# untitled.net
KiCad netlist of a schematic drawn in EAGLE
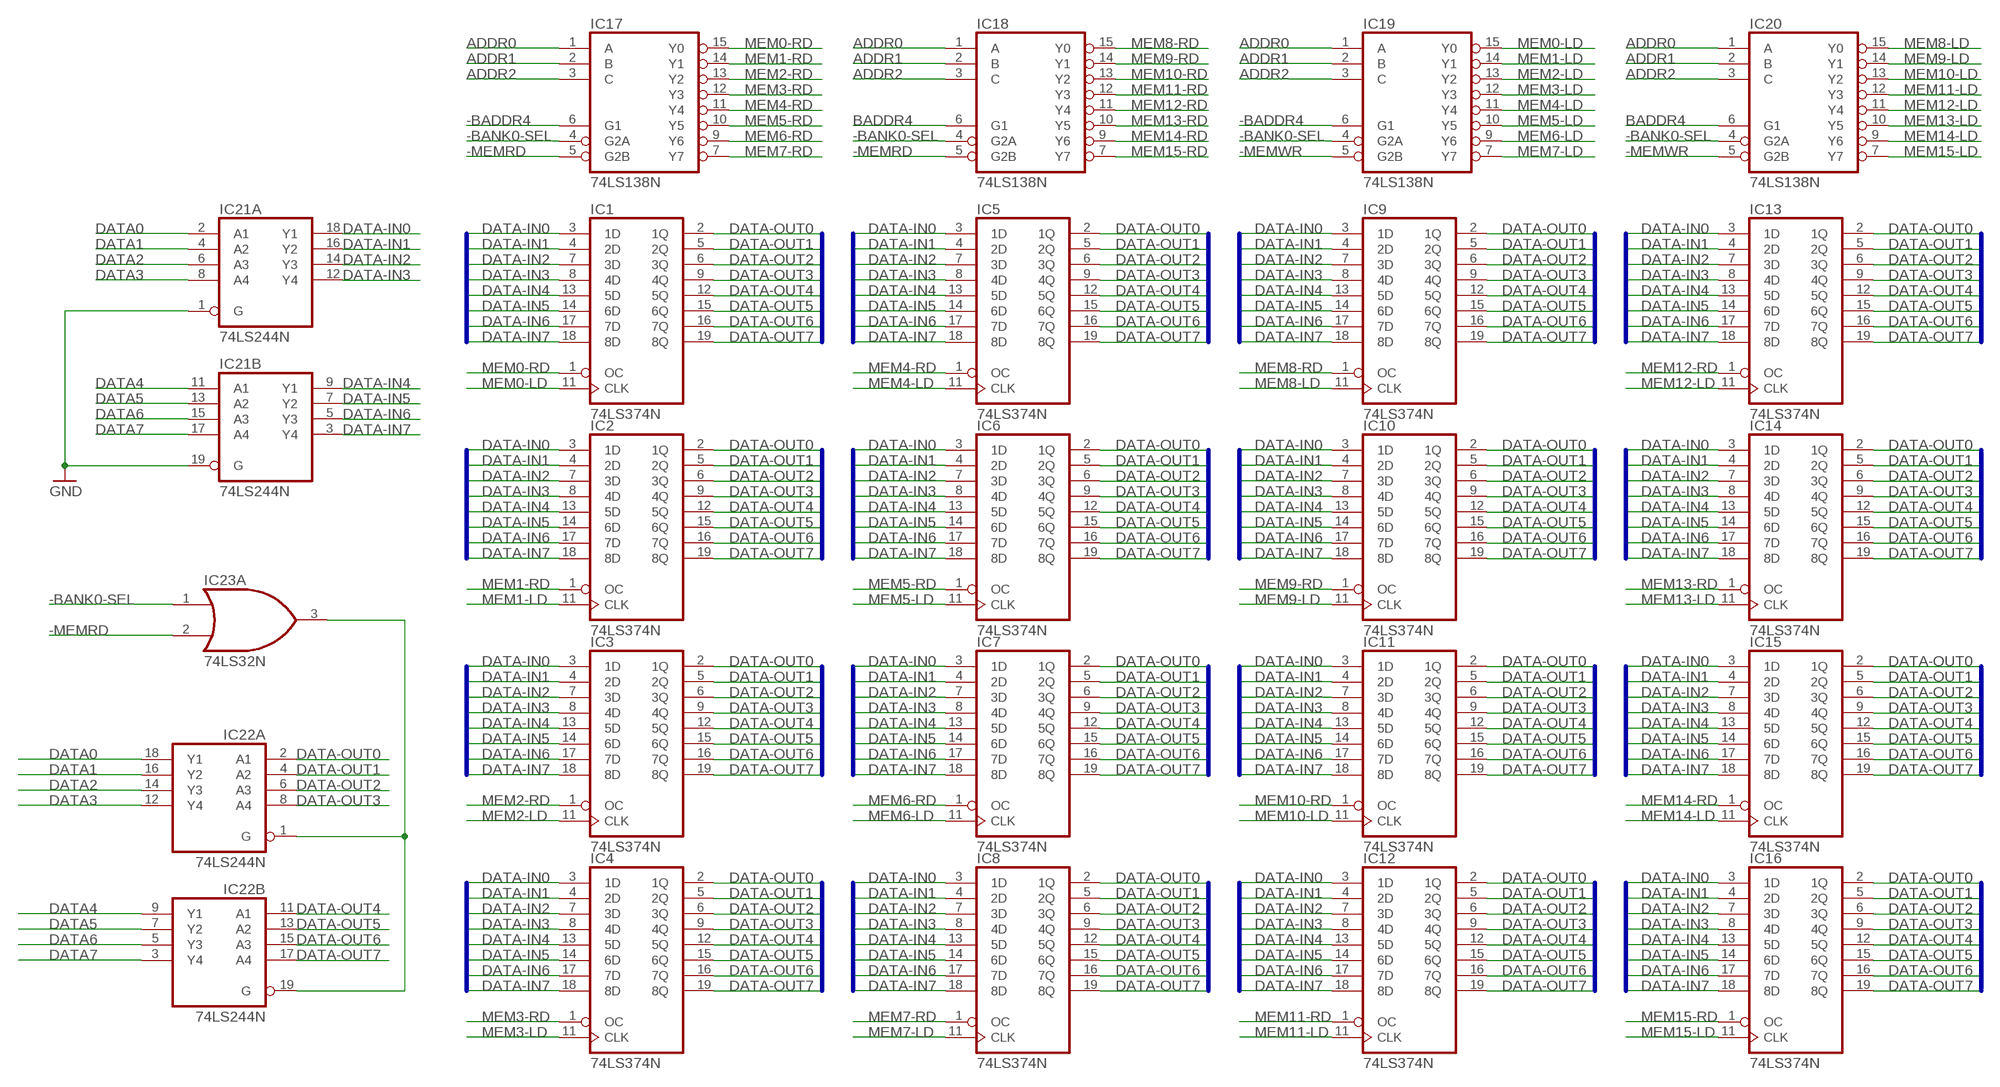
[diagram p0: schematic, sheet 1]
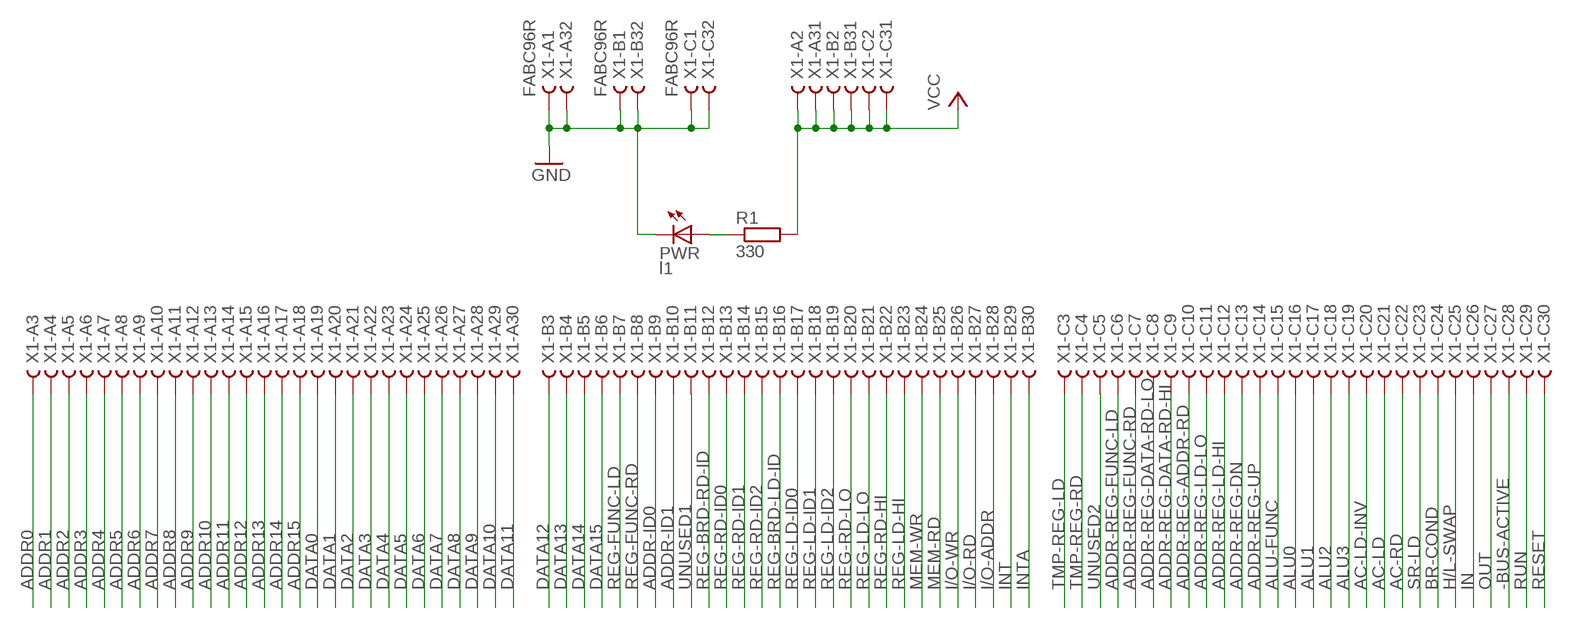
[diagram p1: schematic, sheet 2]
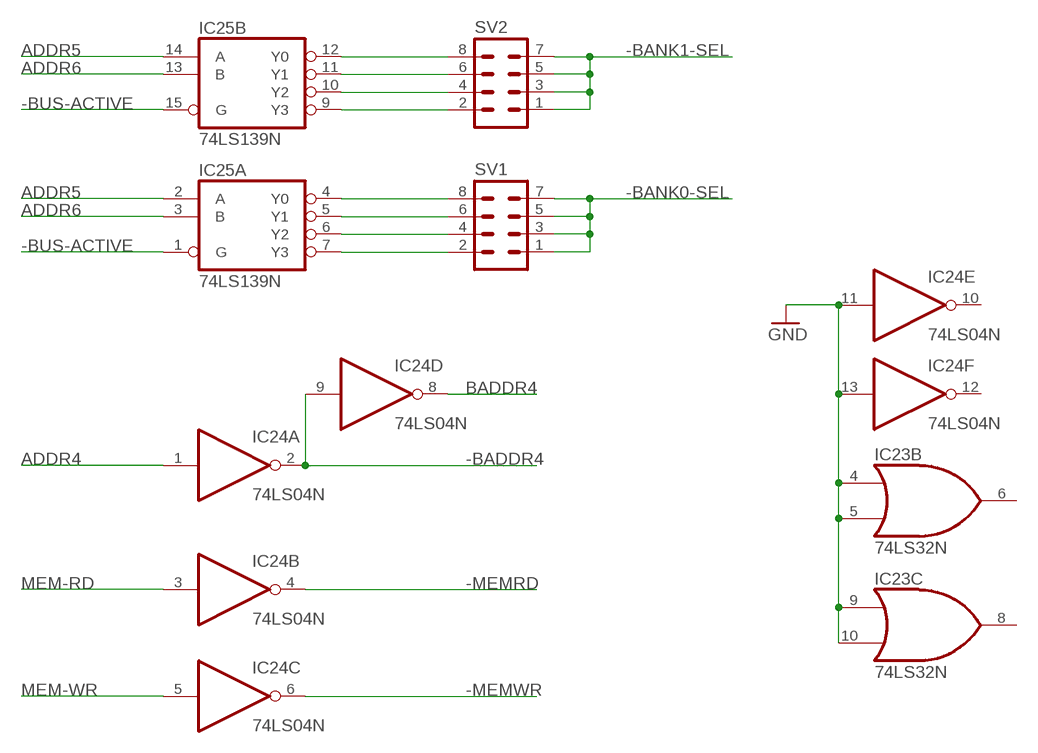
[diagram p2: schematic, sheet 3]
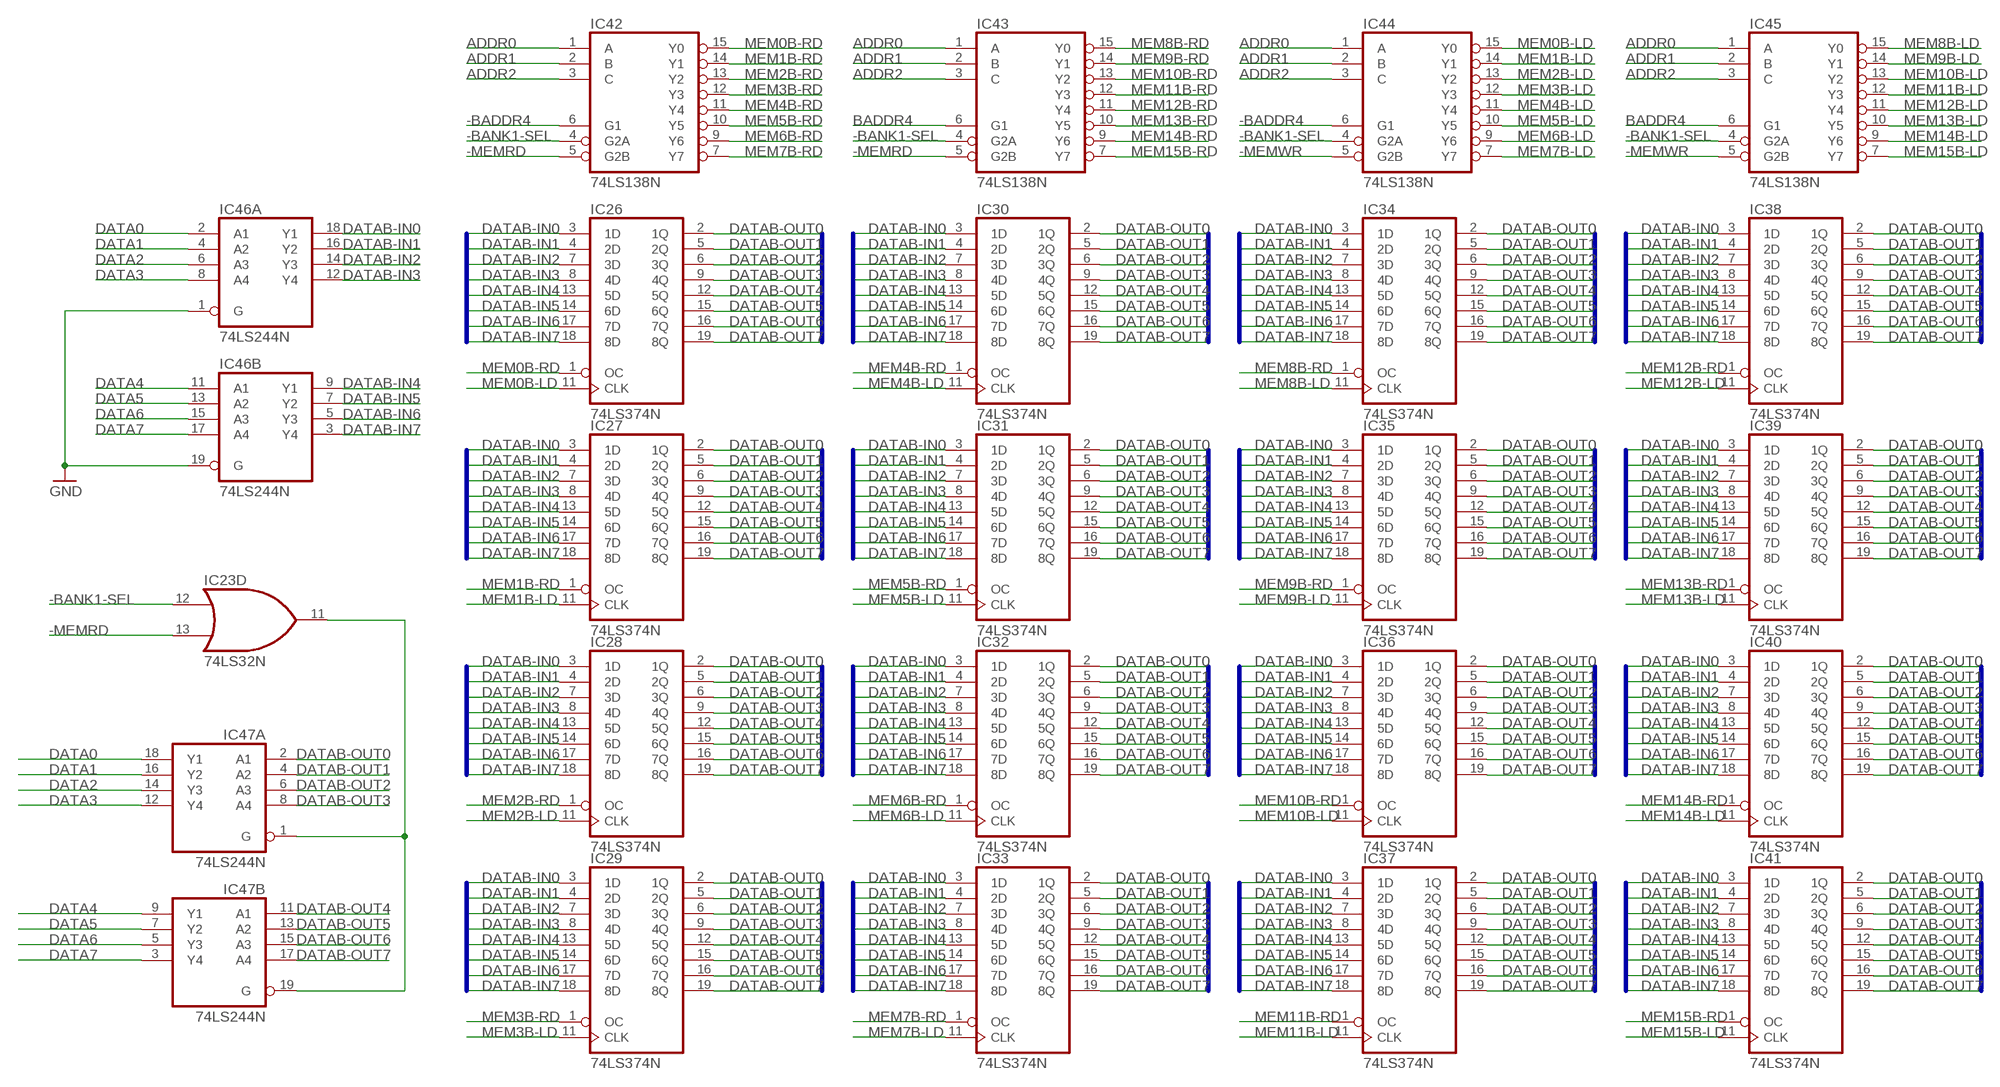
[diagram p3: schematic, sheet 4]

(export (version "E")
  (design (tool "Eeschema 10.0.6"))
  (components
    (comp (ref "PWR")
      (value "l1")
      (footprint "eagle-import:LED5MM")
      (libsource (lib "eagle-import") (part "LED5MM"))
    )
    (comp (ref "R1")
      (value "330")
      (footprint "eagle-import:0207_10")
      (libsource (lib "eagle-import") (part "R0207/10"))
    )
    (comp (ref "X1")
      (value "FABC96R")
      (footprint "eagle-import:FABC96R")
      (libsource (lib "eagle-import") (part "FABC96R"))
    )
    (comp (ref "IC1")
      (value "74LS374N")
      (footprint "eagle-import:DIL20")
      (libsource (lib "eagle-import") (part "74374NLS"))
    )
    (comp (ref "IC2")
      (value "74LS374N")
      (footprint "eagle-import:DIL20")
      (libsource (lib "eagle-import") (part "74374NLS"))
    )
    (comp (ref "IC3")
      (value "74LS374N")
      (footprint "eagle-import:DIL20")
      (libsource (lib "eagle-import") (part "74374NLS"))
    )
    (comp (ref "IC4")
      (value "74LS374N")
      (footprint "eagle-import:DIL20")
      (libsource (lib "eagle-import") (part "74374NLS"))
    )
    (comp (ref "IC5")
      (value "74LS374N")
      (footprint "eagle-import:DIL20")
      (libsource (lib "eagle-import") (part "74374NLS"))
    )
    (comp (ref "IC6")
      (value "74LS374N")
      (footprint "eagle-import:DIL20")
      (libsource (lib "eagle-import") (part "74374NLS"))
    )
    (comp (ref "IC7")
      (value "74LS374N")
      (footprint "eagle-import:DIL20")
      (libsource (lib "eagle-import") (part "74374NLS"))
    )
    (comp (ref "IC8")
      (value "74LS374N")
      (footprint "eagle-import:DIL20")
      (libsource (lib "eagle-import") (part "74374NLS"))
    )
    (comp (ref "IC9")
      (value "74LS374N")
      (footprint "eagle-import:DIL20")
      (libsource (lib "eagle-import") (part "74374NLS"))
    )
    (comp (ref "IC10")
      (value "74LS374N")
      (footprint "eagle-import:DIL20")
      (libsource (lib "eagle-import") (part "74374NLS"))
    )
    (comp (ref "IC11")
      (value "74LS374N")
      (footprint "eagle-import:DIL20")
      (libsource (lib "eagle-import") (part "74374NLS"))
    )
    (comp (ref "IC12")
      (value "74LS374N")
      (footprint "eagle-import:DIL20")
      (libsource (lib "eagle-import") (part "74374NLS"))
    )
    (comp (ref "IC13")
      (value "74LS374N")
      (footprint "eagle-import:DIL20")
      (libsource (lib "eagle-import") (part "74374NLS"))
    )
    (comp (ref "IC14")
      (value "74LS374N")
      (footprint "eagle-import:DIL20")
      (libsource (lib "eagle-import") (part "74374NLS"))
    )
    (comp (ref "IC15")
      (value "74LS374N")
      (footprint "eagle-import:DIL20")
      (libsource (lib "eagle-import") (part "74374NLS"))
    )
    (comp (ref "IC16")
      (value "74LS374N")
      (footprint "eagle-import:DIL20")
      (libsource (lib "eagle-import") (part "74374NLS"))
    )
    (comp (ref "IC17")
      (value "74LS138N")
      (footprint "eagle-import:DIL16")
      (libsource (lib "eagle-import") (part "74138NLS"))
    )
    (comp (ref "IC18")
      (value "74LS138N")
      (footprint "eagle-import:DIL16")
      (libsource (lib "eagle-import") (part "74138NLS"))
    )
    (comp (ref "IC19")
      (value "74LS138N")
      (footprint "eagle-import:DIL16")
      (libsource (lib "eagle-import") (part "74138NLS"))
    )
    (comp (ref "IC20")
      (value "74LS138N")
      (footprint "eagle-import:DIL16")
      (libsource (lib "eagle-import") (part "74138NLS"))
    )
    (comp (ref "IC21")
      (value "74LS244N")
      (footprint "eagle-import:DIL20")
      (libsource (lib "eagle-import") (part "74244NLS"))
    )
    (comp (ref "IC22")
      (value "74LS244N")
      (footprint "eagle-import:DIL20")
      (libsource (lib "eagle-import") (part "74244NLS"))
    )
    (comp (ref "IC23")
      (value "74LS32N")
      (footprint "eagle-import:DIL14")
      (libsource (lib "eagle-import") (part "7432NLS"))
    )
    (comp (ref "IC24")
      (value "74LS04N")
      (footprint "eagle-import:DIL14")
      (libsource (lib "eagle-import") (part "7404NLS"))
    )
    (comp (ref "IC25")
      (value "74LS139N")
      (footprint "eagle-import:DIL16")
      (libsource (lib "eagle-import") (part "74139NLS"))
    )
    (comp (ref "SV1")
      (value "MA04-2")
      (footprint "eagle-import:MA04-2")
      (libsource (lib "eagle-import") (part "MA04-2"))
    )
    (comp (ref "SV2")
      (value "MA04-2")
      (footprint "eagle-import:MA04-2")
      (libsource (lib "eagle-import") (part "MA04-2"))
    )
    (comp (ref "IC26")
      (value "74LS374N")
      (footprint "eagle-import:DIL20")
      (libsource (lib "eagle-import") (part "74374NLS"))
    )
    (comp (ref "IC27")
      (value "74LS374N")
      (footprint "eagle-import:DIL20")
      (libsource (lib "eagle-import") (part "74374NLS"))
    )
    (comp (ref "IC28")
      (value "74LS374N")
      (footprint "eagle-import:DIL20")
      (libsource (lib "eagle-import") (part "74374NLS"))
    )
    (comp (ref "IC29")
      (value "74LS374N")
      (footprint "eagle-import:DIL20")
      (libsource (lib "eagle-import") (part "74374NLS"))
    )
    (comp (ref "IC30")
      (value "74LS374N")
      (footprint "eagle-import:DIL20")
      (libsource (lib "eagle-import") (part "74374NLS"))
    )
    (comp (ref "IC31")
      (value "74LS374N")
      (footprint "eagle-import:DIL20")
      (libsource (lib "eagle-import") (part "74374NLS"))
    )
    (comp (ref "IC32")
      (value "74LS374N")
      (footprint "eagle-import:DIL20")
      (libsource (lib "eagle-import") (part "74374NLS"))
    )
    (comp (ref "IC33")
      (value "74LS374N")
      (footprint "eagle-import:DIL20")
      (libsource (lib "eagle-import") (part "74374NLS"))
    )
    (comp (ref "IC34")
      (value "74LS374N")
      (footprint "eagle-import:DIL20")
      (libsource (lib "eagle-import") (part "74374NLS"))
    )
    (comp (ref "IC35")
      (value "74LS374N")
      (footprint "eagle-import:DIL20")
      (libsource (lib "eagle-import") (part "74374NLS"))
    )
    (comp (ref "IC36")
      (value "74LS374N")
      (footprint "eagle-import:DIL20")
      (libsource (lib "eagle-import") (part "74374NLS"))
    )
    (comp (ref "IC37")
      (value "74LS374N")
      (footprint "eagle-import:DIL20")
      (libsource (lib "eagle-import") (part "74374NLS"))
    )
    (comp (ref "IC38")
      (value "74LS374N")
      (footprint "eagle-import:DIL20")
      (libsource (lib "eagle-import") (part "74374NLS"))
    )
    (comp (ref "IC39")
      (value "74LS374N")
      (footprint "eagle-import:DIL20")
      (libsource (lib "eagle-import") (part "74374NLS"))
    )
    (comp (ref "IC40")
      (value "74LS374N")
      (footprint "eagle-import:DIL20")
      (libsource (lib "eagle-import") (part "74374NLS"))
    )
    (comp (ref "IC41")
      (value "74LS374N")
      (footprint "eagle-import:DIL20")
      (libsource (lib "eagle-import") (part "74374NLS"))
    )
    (comp (ref "IC42")
      (value "74LS138N")
      (footprint "eagle-import:DIL16")
      (libsource (lib "eagle-import") (part "74138NLS"))
    )
    (comp (ref "IC43")
      (value "74LS138N")
      (footprint "eagle-import:DIL16")
      (libsource (lib "eagle-import") (part "74138NLS"))
    )
    (comp (ref "IC44")
      (value "74LS138N")
      (footprint "eagle-import:DIL16")
      (libsource (lib "eagle-import") (part "74138NLS"))
    )
    (comp (ref "IC45")
      (value "74LS138N")
      (footprint "eagle-import:DIL16")
      (libsource (lib "eagle-import") (part "74138NLS"))
    )
    (comp (ref "IC46")
      (value "74LS244N")
      (footprint "eagle-import:DIL20")
      (libsource (lib "eagle-import") (part "74244NLS"))
    )
    (comp (ref "IC47")
      (value "74LS244N")
      (footprint "eagle-import:DIL20")
      (libsource (lib "eagle-import") (part "74244NLS"))
    )
  )
  (nets
    (net (code "1") (name "-BADDR4") (class "Default")
      (node (ref "IC17") (pin "6") (pinfunction "G1_6") (pintype "input"))
      (node (ref "IC19") (pin "6") (pinfunction "G1_6") (pintype "input"))
      (node (ref "IC24") (pin "2") (pinfunction "O_2") (pintype "output"))
      (node (ref "IC24") (pin "9") (pinfunction "I_9") (pintype "input"))
      (node (ref "IC42") (pin "6") (pinfunction "G1_6") (pintype "input"))
      (node (ref "IC44") (pin "6") (pinfunction "G1_6") (pintype "input"))
    )
    (net (code "2") (name "-BANK0-SEL") (class "Default")
      (node (ref "IC17") (pin "4") (pinfunction "G2A_4") (pintype "input"))
      (node (ref "IC18") (pin "4") (pinfunction "G2A_4") (pintype "input"))
      (node (ref "IC19") (pin "4") (pinfunction "G2A_4") (pintype "input"))
      (node (ref "IC20") (pin "4") (pinfunction "G2A_4") (pintype "input"))
      (node (ref "IC23") (pin "1") (pinfunction "I0_1") (pintype "input"))
      (node (ref "SV1") (pin "1") (pinfunction "1_1") (pintype "passive"))
      (node (ref "SV1") (pin "3") (pinfunction "3_3") (pintype "passive"))
      (node (ref "SV1") (pin "5") (pinfunction "5_5") (pintype "passive"))
      (node (ref "SV1") (pin "7") (pinfunction "7_7") (pintype "passive"))
    )
    (net (code "3") (name "-BANK1-SEL") (class "Default")
      (node (ref "IC23") (pin "12") (pinfunction "I0_12") (pintype "input"))
      (node (ref "IC42") (pin "4") (pinfunction "G2A_4") (pintype "input"))
      (node (ref "IC43") (pin "4") (pinfunction "G2A_4") (pintype "input"))
      (node (ref "IC44") (pin "4") (pinfunction "G2A_4") (pintype "input"))
      (node (ref "IC45") (pin "4") (pinfunction "G2A_4") (pintype "input"))
      (node (ref "SV2") (pin "1") (pinfunction "1_1") (pintype "passive"))
      (node (ref "SV2") (pin "3") (pinfunction "3_3") (pintype "passive"))
      (node (ref "SV2") (pin "5") (pinfunction "5_5") (pintype "passive"))
      (node (ref "SV2") (pin "7") (pinfunction "7_7") (pintype "passive"))
    )
    (net (code "4") (name "-BUS-ACTIVE") (class "Default")
      (node (ref "IC25") (pin "1") (pinfunction "G_1") (pintype "input"))
      (node (ref "IC25") (pin "15") (pinfunction "G_15") (pintype "input"))
      (node (ref "X1") (pin "C28") (pinfunction "B_C28") (pintype "passive"))
    )
    (net (code "5") (name "-MEMRD") (class "Default")
      (node (ref "IC17") (pin "5") (pinfunction "G2B_5") (pintype "input"))
      (node (ref "IC18") (pin "5") (pinfunction "G2B_5") (pintype "input"))
      (node (ref "IC23") (pin "13") (pinfunction "I1_13") (pintype "input"))
      (node (ref "IC23") (pin "2") (pinfunction "I1_2") (pintype "input"))
      (node (ref "IC24") (pin "4") (pinfunction "O_4") (pintype "output"))
      (node (ref "IC42") (pin "5") (pinfunction "G2B_5") (pintype "input"))
      (node (ref "IC43") (pin "5") (pinfunction "G2B_5") (pintype "input"))
    )
    (net (code "6") (name "-MEMWR") (class "Default")
      (node (ref "IC19") (pin "5") (pinfunction "G2B_5") (pintype "input"))
      (node (ref "IC20") (pin "5") (pinfunction "G2B_5") (pintype "input"))
      (node (ref "IC24") (pin "6") (pinfunction "O_6") (pintype "output"))
      (node (ref "IC44") (pin "5") (pinfunction "G2B_5") (pintype "input"))
      (node (ref "IC45") (pin "5") (pinfunction "G2B_5") (pintype "input"))
    )
    (net (code "7") (name "AC-LD") (class "Default")
      (node (ref "X1") (pin "C21") (pinfunction "B_C21") (pintype "passive"))
    )
    (net (code "8") (name "AC-LD-INV") (class "Default")
      (node (ref "X1") (pin "C20") (pinfunction "B_C20") (pintype "passive"))
    )
    (net (code "9") (name "AC-RD") (class "Default")
      (node (ref "X1") (pin "C22") (pinfunction "B_C22") (pintype "passive"))
    )
    (net (code "10") (name "ADDR-ID0") (class "Default")
      (node (ref "X1") (pin "B9") (pinfunction "B_B9") (pintype "passive"))
    )
    (net (code "11") (name "ADDR-ID1") (class "Default")
      (node (ref "X1") (pin "B10") (pinfunction "B_B10") (pintype "passive"))
    )
    (net (code "12") (name "ADDR-REG-ADDR-RD") (class "Default")
      (node (ref "X1") (pin "C10") (pinfunction "B_C10") (pintype "passive"))
    )
    (net (code "13") (name "ADDR-REG-DATA-RD-HI") (class "Default")
      (node (ref "X1") (pin "C9") (pinfunction "B_C9") (pintype "passive"))
    )
    (net (code "14") (name "ADDR-REG-DATA-RD-LO") (class "Default")
      (node (ref "X1") (pin "C8") (pinfunction "B_C8") (pintype "passive"))
    )
    (net (code "15") (name "ADDR-REG-DN") (class "Default")
      (node (ref "X1") (pin "C13") (pinfunction "B_C13") (pintype "passive"))
    )
    (net (code "16") (name "ADDR-REG-FUNC-LD") (class "Default")
      (node (ref "X1") (pin "C6") (pinfunction "B_C6") (pintype "passive"))
    )
    (net (code "17") (name "ADDR-REG-FUNC-RD") (class "Default")
      (node (ref "X1") (pin "C7") (pinfunction "B_C7") (pintype "passive"))
    )
    (net (code "18") (name "ADDR-REG-LD-HI") (class "Default")
      (node (ref "X1") (pin "C12") (pinfunction "B_C12") (pintype "passive"))
    )
    (net (code "19") (name "ADDR-REG-LD-LO") (class "Default")
      (node (ref "X1") (pin "C11") (pinfunction "B_C11") (pintype "passive"))
    )
    (net (code "20") (name "ADDR-REG-UP") (class "Default")
      (node (ref "X1") (pin "C14") (pinfunction "B_C14") (pintype "passive"))
    )
    (net (code "21") (name "ADDR0") (class "Default")
      (node (ref "IC17") (pin "1") (pinfunction "A_1") (pintype "input"))
      (node (ref "IC18") (pin "1") (pinfunction "A_1") (pintype "input"))
      (node (ref "IC19") (pin "1") (pinfunction "A_1") (pintype "input"))
      (node (ref "IC20") (pin "1") (pinfunction "A_1") (pintype "input"))
      (node (ref "IC42") (pin "1") (pinfunction "A_1") (pintype "input"))
      (node (ref "IC43") (pin "1") (pinfunction "A_1") (pintype "input"))
      (node (ref "IC44") (pin "1") (pinfunction "A_1") (pintype "input"))
      (node (ref "IC45") (pin "1") (pinfunction "A_1") (pintype "input"))
      (node (ref "X1") (pin "A3") (pinfunction "B_A3") (pintype "passive"))
    )
    (net (code "22") (name "ADDR1") (class "Default")
      (node (ref "IC17") (pin "2") (pinfunction "B_2") (pintype "input"))
      (node (ref "IC18") (pin "2") (pinfunction "B_2") (pintype "input"))
      (node (ref "IC19") (pin "2") (pinfunction "B_2") (pintype "input"))
      (node (ref "IC20") (pin "2") (pinfunction "B_2") (pintype "input"))
      (node (ref "IC42") (pin "2") (pinfunction "B_2") (pintype "input"))
      (node (ref "IC43") (pin "2") (pinfunction "B_2") (pintype "input"))
      (node (ref "IC44") (pin "2") (pinfunction "B_2") (pintype "input"))
      (node (ref "IC45") (pin "2") (pinfunction "B_2") (pintype "input"))
      (node (ref "X1") (pin "A4") (pinfunction "B_A4") (pintype "passive"))
    )
    (net (code "23") (name "ADDR2") (class "Default")
      (node (ref "IC17") (pin "3") (pinfunction "C_3") (pintype "input"))
      (node (ref "IC18") (pin "3") (pinfunction "C_3") (pintype "input"))
      (node (ref "IC19") (pin "3") (pinfunction "C_3") (pintype "input"))
      (node (ref "IC20") (pin "3") (pinfunction "C_3") (pintype "input"))
      (node (ref "IC42") (pin "3") (pinfunction "C_3") (pintype "input"))
      (node (ref "IC43") (pin "3") (pinfunction "C_3") (pintype "input"))
      (node (ref "IC44") (pin "3") (pinfunction "C_3") (pintype "input"))
      (node (ref "IC45") (pin "3") (pinfunction "C_3") (pintype "input"))
      (node (ref "X1") (pin "A5") (pinfunction "B_A5") (pintype "passive"))
    )
    (net (code "24") (name "ADDR3") (class "Default")
      (node (ref "X1") (pin "A6") (pinfunction "B_A6") (pintype "passive"))
    )
    (net (code "25") (name "ADDR4") (class "Default")
      (node (ref "IC24") (pin "1") (pinfunction "I_1") (pintype "input"))
      (node (ref "X1") (pin "A7") (pinfunction "B_A7") (pintype "passive"))
    )
    (net (code "26") (name "ADDR5") (class "Default")
      (node (ref "IC25") (pin "14") (pinfunction "A_14") (pintype "input"))
      (node (ref "IC25") (pin "2") (pinfunction "A_2") (pintype "input"))
      (node (ref "X1") (pin "A8") (pinfunction "B_A8") (pintype "passive"))
    )
    (net (code "27") (name "ADDR6") (class "Default")
      (node (ref "IC25") (pin "13") (pinfunction "B_13") (pintype "input"))
      (node (ref "IC25") (pin "3") (pinfunction "B_3") (pintype "input"))
      (node (ref "X1") (pin "A9") (pinfunction "B_A9") (pintype "passive"))
    )
    (net (code "28") (name "ADDR7") (class "Default")
      (node (ref "X1") (pin "A10") (pinfunction "B_A10") (pintype "passive"))
    )
    (net (code "29") (name "ADDR8") (class "Default")
      (node (ref "X1") (pin "A11") (pinfunction "B_A11") (pintype "passive"))
    )
    (net (code "30") (name "ADDR9") (class "Default")
      (node (ref "X1") (pin "A12") (pinfunction "B_A12") (pintype "passive"))
    )
    (net (code "31") (name "ADDR10") (class "Default")
      (node (ref "X1") (pin "A13") (pinfunction "B_A13") (pintype "passive"))
    )
    (net (code "32") (name "ADDR11") (class "Default")
      (node (ref "X1") (pin "A14") (pinfunction "B_A14") (pintype "passive"))
    )
    (net (code "33") (name "ADDR12") (class "Default")
      (node (ref "X1") (pin "A15") (pinfunction "B_A15") (pintype "passive"))
    )
    (net (code "34") (name "ADDR13") (class "Default")
      (node (ref "X1") (pin "A16") (pinfunction "B_A16") (pintype "passive"))
    )
    (net (code "35") (name "ADDR14") (class "Default")
      (node (ref "X1") (pin "A17") (pinfunction "B_A17") (pintype "passive"))
    )
    (net (code "36") (name "ADDR15") (class "Default")
      (node (ref "X1") (pin "A18") (pinfunction "B_A18") (pintype "passive"))
    )
    (net (code "37") (name "ALU-FUNC") (class "Default")
      (node (ref "X1") (pin "C15") (pinfunction "B_C15") (pintype "passive"))
    )
    (net (code "38") (name "ALU0") (class "Default")
      (node (ref "X1") (pin "C16") (pinfunction "B_C16") (pintype "passive"))
    )
    (net (code "39") (name "ALU1") (class "Default")
      (node (ref "X1") (pin "C17") (pinfunction "B_C17") (pintype "passive"))
    )
    (net (code "40") (name "ALU2") (class "Default")
      (node (ref "X1") (pin "C18") (pinfunction "B_C18") (pintype "passive"))
    )
    (net (code "41") (name "ALU3") (class "Default")
      (node (ref "X1") (pin "C19") (pinfunction "B_C19") (pintype "passive"))
    )
    (net (code "42") (name "BADDR4") (class "Default")
      (node (ref "IC18") (pin "6") (pinfunction "G1_6") (pintype "input"))
      (node (ref "IC20") (pin "6") (pinfunction "G1_6") (pintype "input"))
      (node (ref "IC24") (pin "8") (pinfunction "O_8") (pintype "output"))
      (node (ref "IC43") (pin "6") (pinfunction "G1_6") (pintype "input"))
      (node (ref "IC45") (pin "6") (pinfunction "G1_6") (pintype "input"))
    )
    (net (code "43") (name "BR-COND") (class "Default")
      (node (ref "X1") (pin "C24") (pinfunction "B_C24") (pintype "passive"))
    )
    (net (code "44") (name "DATA-IN0") (class "Default")
      (node (ref "IC1") (pin "3") (pinfunction "1D_3") (pintype "input"))
      (node (ref "IC10") (pin "3") (pinfunction "1D_3") (pintype "input"))
      (node (ref "IC11") (pin "3") (pinfunction "1D_3") (pintype "input"))
      (node (ref "IC12") (pin "3") (pinfunction "1D_3") (pintype "input"))
      (node (ref "IC13") (pin "3") (pinfunction "1D_3") (pintype "input"))
      (node (ref "IC14") (pin "3") (pinfunction "1D_3") (pintype "input"))
      (node (ref "IC15") (pin "3") (pinfunction "1D_3") (pintype "input"))
      (node (ref "IC16") (pin "3") (pinfunction "1D_3") (pintype "input"))
      (node (ref "IC2") (pin "3") (pinfunction "1D_3") (pintype "input"))
      (node (ref "IC21") (pin "18") (pinfunction "Y1_18") (pintype "tri_state"))
      (node (ref "IC3") (pin "3") (pinfunction "1D_3") (pintype "input"))
      (node (ref "IC4") (pin "3") (pinfunction "1D_3") (pintype "input"))
      (node (ref "IC5") (pin "3") (pinfunction "1D_3") (pintype "input"))
      (node (ref "IC6") (pin "3") (pinfunction "1D_3") (pintype "input"))
      (node (ref "IC7") (pin "3") (pinfunction "1D_3") (pintype "input"))
      (node (ref "IC8") (pin "3") (pinfunction "1D_3") (pintype "input"))
      (node (ref "IC9") (pin "3") (pinfunction "1D_3") (pintype "input"))
    )
    (net (code "45") (name "DATA-IN1") (class "Default")
      (node (ref "IC1") (pin "4") (pinfunction "2D_4") (pintype "input"))
      (node (ref "IC10") (pin "4") (pinfunction "2D_4") (pintype "input"))
      (node (ref "IC11") (pin "4") (pinfunction "2D_4") (pintype "input"))
      (node (ref "IC12") (pin "4") (pinfunction "2D_4") (pintype "input"))
      (node (ref "IC13") (pin "4") (pinfunction "2D_4") (pintype "input"))
      (node (ref "IC14") (pin "4") (pinfunction "2D_4") (pintype "input"))
      (node (ref "IC15") (pin "4") (pinfunction "2D_4") (pintype "input"))
      (node (ref "IC16") (pin "4") (pinfunction "2D_4") (pintype "input"))
      (node (ref "IC2") (pin "4") (pinfunction "2D_4") (pintype "input"))
      (node (ref "IC21") (pin "16") (pinfunction "Y2_16") (pintype "tri_state"))
      (node (ref "IC3") (pin "4") (pinfunction "2D_4") (pintype "input"))
      (node (ref "IC4") (pin "4") (pinfunction "2D_4") (pintype "input"))
      (node (ref "IC5") (pin "4") (pinfunction "2D_4") (pintype "input"))
      (node (ref "IC6") (pin "4") (pinfunction "2D_4") (pintype "input"))
      (node (ref "IC7") (pin "4") (pinfunction "2D_4") (pintype "input"))
      (node (ref "IC8") (pin "4") (pinfunction "2D_4") (pintype "input"))
      (node (ref "IC9") (pin "4") (pinfunction "2D_4") (pintype "input"))
    )
    (net (code "46") (name "DATA-IN2") (class "Default")
      (node (ref "IC1") (pin "7") (pinfunction "3D_7") (pintype "input"))
      (node (ref "IC10") (pin "7") (pinfunction "3D_7") (pintype "input"))
      (node (ref "IC11") (pin "7") (pinfunction "3D_7") (pintype "input"))
      (node (ref "IC12") (pin "7") (pinfunction "3D_7") (pintype "input"))
      (node (ref "IC13") (pin "7") (pinfunction "3D_7") (pintype "input"))
      (node (ref "IC14") (pin "7") (pinfunction "3D_7") (pintype "input"))
      (node (ref "IC15") (pin "7") (pinfunction "3D_7") (pintype "input"))
      (node (ref "IC16") (pin "7") (pinfunction "3D_7") (pintype "input"))
      (node (ref "IC2") (pin "7") (pinfunction "3D_7") (pintype "input"))
      (node (ref "IC21") (pin "14") (pinfunction "Y3_14") (pintype "tri_state"))
      (node (ref "IC3") (pin "7") (pinfunction "3D_7") (pintype "input"))
      (node (ref "IC4") (pin "7") (pinfunction "3D_7") (pintype "input"))
      (node (ref "IC5") (pin "7") (pinfunction "3D_7") (pintype "input"))
      (node (ref "IC6") (pin "7") (pinfunction "3D_7") (pintype "input"))
      (node (ref "IC7") (pin "7") (pinfunction "3D_7") (pintype "input"))
      (node (ref "IC8") (pin "7") (pinfunction "3D_7") (pintype "input"))
      (node (ref "IC9") (pin "7") (pinfunction "3D_7") (pintype "input"))
    )
    (net (code "47") (name "DATA-IN3") (class "Default")
      (node (ref "IC1") (pin "8") (pinfunction "4D_8") (pintype "input"))
      (node (ref "IC10") (pin "8") (pinfunction "4D_8") (pintype "input"))
      (node (ref "IC11") (pin "8") (pinfunction "4D_8") (pintype "input"))
      (node (ref "IC12") (pin "8") (pinfunction "4D_8") (pintype "input"))
      (node (ref "IC13") (pin "8") (pinfunction "4D_8") (pintype "input"))
      (node (ref "IC14") (pin "8") (pinfunction "4D_8") (pintype "input"))
      (node (ref "IC15") (pin "8") (pinfunction "4D_8") (pintype "input"))
      (node (ref "IC16") (pin "8") (pinfunction "4D_8") (pintype "input"))
      (node (ref "IC2") (pin "8") (pinfunction "4D_8") (pintype "input"))
      (node (ref "IC21") (pin "12") (pinfunction "Y4_12") (pintype "tri_state"))
      (node (ref "IC3") (pin "8") (pinfunction "4D_8") (pintype "input"))
      (node (ref "IC4") (pin "8") (pinfunction "4D_8") (pintype "input"))
      (node (ref "IC5") (pin "8") (pinfunction "4D_8") (pintype "input"))
      (node (ref "IC6") (pin "8") (pinfunction "4D_8") (pintype "input"))
      (node (ref "IC7") (pin "8") (pinfunction "4D_8") (pintype "input"))
      (node (ref "IC8") (pin "8") (pinfunction "4D_8") (pintype "input"))
      (node (ref "IC9") (pin "8") (pinfunction "4D_8") (pintype "input"))
    )
    (net (code "48") (name "DATA-IN4") (class "Default")
      (node (ref "IC1") (pin "13") (pinfunction "5D_13") (pintype "input"))
      (node (ref "IC10") (pin "13") (pinfunction "5D_13") (pintype "input"))
      (node (ref "IC11") (pin "13") (pinfunction "5D_13") (pintype "input"))
      (node (ref "IC12") (pin "13") (pinfunction "5D_13") (pintype "input"))
      (node (ref "IC13") (pin "13") (pinfunction "5D_13") (pintype "input"))
      (node (ref "IC14") (pin "13") (pinfunction "5D_13") (pintype "input"))
      (node (ref "IC15") (pin "13") (pinfunction "5D_13") (pintype "input"))
      (node (ref "IC16") (pin "13") (pinfunction "5D_13") (pintype "input"))
      (node (ref "IC2") (pin "13") (pinfunction "5D_13") (pintype "input"))
      (node (ref "IC21") (pin "9") (pinfunction "Y1_9") (pintype "tri_state"))
      (node (ref "IC3") (pin "13") (pinfunction "5D_13") (pintype "input"))
      (node (ref "IC4") (pin "13") (pinfunction "5D_13") (pintype "input"))
      (node (ref "IC5") (pin "13") (pinfunction "5D_13") (pintype "input"))
      (node (ref "IC6") (pin "13") (pinfunction "5D_13") (pintype "input"))
      (node (ref "IC7") (pin "13") (pinfunction "5D_13") (pintype "input"))
      (node (ref "IC8") (pin "13") (pinfunction "5D_13") (pintype "input"))
      (node (ref "IC9") (pin "13") (pinfunction "5D_13") (pintype "input"))
    )
    (net (code "49") (name "DATA-IN5") (class "Default")
      (node (ref "IC1") (pin "14") (pinfunction "6D_14") (pintype "input"))
      (node (ref "IC10") (pin "14") (pinfunction "6D_14") (pintype "input"))
      (node (ref "IC11") (pin "14") (pinfunction "6D_14") (pintype "input"))
      (node (ref "IC12") (pin "14") (pinfunction "6D_14") (pintype "input"))
      (node (ref "IC13") (pin "14") (pinfunction "6D_14") (pintype "input"))
      (node (ref "IC14") (pin "14") (pinfunction "6D_14") (pintype "input"))
      (node (ref "IC15") (pin "14") (pinfunction "6D_14") (pintype "input"))
      (node (ref "IC16") (pin "14") (pinfunction "6D_14") (pintype "input"))
      (node (ref "IC2") (pin "14") (pinfunction "6D_14") (pintype "input"))
      (node (ref "IC21") (pin "7") (pinfunction "Y2_7") (pintype "tri_state"))
      (node (ref "IC3") (pin "14") (pinfunction "6D_14") (pintype "input"))
      (node (ref "IC4") (pin "14") (pinfunction "6D_14") (pintype "input"))
      (node (ref "IC5") (pin "14") (pinfunction "6D_14") (pintype "input"))
      (node (ref "IC6") (pin "14") (pinfunction "6D_14") (pintype "input"))
      (node (ref "IC7") (pin "14") (pinfunction "6D_14") (pintype "input"))
      (node (ref "IC8") (pin "14") (pinfunction "6D_14") (pintype "input"))
      (node (ref "IC9") (pin "14") (pinfunction "6D_14") (pintype "input"))
    )
    (net (code "50") (name "DATA-IN6") (class "Default")
      (node (ref "IC1") (pin "17") (pinfunction "7D_17") (pintype "input"))
      (node (ref "IC10") (pin "17") (pinfunction "7D_17") (pintype "input"))
      (node (ref "IC11") (pin "17") (pinfunction "7D_17") (pintype "input"))
      (node (ref "IC12") (pin "17") (pinfunction "7D_17") (pintype "input"))
      (node (ref "IC13") (pin "17") (pinfunction "7D_17") (pintype "input"))
      (node (ref "IC14") (pin "17") (pinfunction "7D_17") (pintype "input"))
      (node (ref "IC15") (pin "17") (pinfunction "7D_17") (pintype "input"))
      (node (ref "IC16") (pin "17") (pinfunction "7D_17") (pintype "input"))
      (node (ref "IC2") (pin "17") (pinfunction "7D_17") (pintype "input"))
      (node (ref "IC21") (pin "5") (pinfunction "Y3_5") (pintype "tri_state"))
      (node (ref "IC3") (pin "17") (pinfunction "7D_17") (pintype "input"))
      (node (ref "IC4") (pin "17") (pinfunction "7D_17") (pintype "input"))
      (node (ref "IC5") (pin "17") (pinfunction "7D_17") (pintype "input"))
      (node (ref "IC6") (pin "17") (pinfunction "7D_17") (pintype "input"))
      (node (ref "IC7") (pin "17") (pinfunction "7D_17") (pintype "input"))
      (node (ref "IC8") (pin "17") (pinfunction "7D_17") (pintype "input"))
      (node (ref "IC9") (pin "17") (pinfunction "7D_17") (pintype "input"))
    )
    (net (code "51") (name "DATA-IN7") (class "Default")
      (node (ref "IC1") (pin "18") (pinfunction "8D_18") (pintype "input"))
      (node (ref "IC10") (pin "18") (pinfunction "8D_18") (pintype "input"))
      (node (ref "IC11") (pin "18") (pinfunction "8D_18") (pintype "input"))
      (node (ref "IC12") (pin "18") (pinfunction "8D_18") (pintype "input"))
      (node (ref "IC13") (pin "18") (pinfunction "8D_18") (pintype "input"))
      (node (ref "IC14") (pin "18") (pinfunction "8D_18") (pintype "input"))
      (node (ref "IC15") (pin "18") (pinfunction "8D_18") (pintype "input"))
      (node (ref "IC16") (pin "18") (pinfunction "8D_18") (pintype "input"))
      (node (ref "IC2") (pin "18") (pinfunction "8D_18") (pintype "input"))
      (node (ref "IC21") (pin "3") (pinfunction "Y4_3") (pintype "tri_state"))
      (node (ref "IC3") (pin "18") (pinfunction "8D_18") (pintype "input"))
      (node (ref "IC4") (pin "18") (pinfunction "8D_18") (pintype "input"))
      (node (ref "IC5") (pin "18") (pinfunction "8D_18") (pintype "input"))
      (node (ref "IC6") (pin "18") (pinfunction "8D_18") (pintype "input"))
      (node (ref "IC7") (pin "18") (pinfunction "8D_18") (pintype "input"))
      (node (ref "IC8") (pin "18") (pinfunction "8D_18") (pintype "input"))
      (node (ref "IC9") (pin "18") (pinfunction "8D_18") (pintype "input"))
    )
    (net (code "52") (name "DATA-OUT0") (class "Default")
      (node (ref "IC1") (pin "2") (pinfunction "1Q_2") (pintype "tri_state"))
      (node (ref "IC10") (pin "2") (pinfunction "1Q_2") (pintype "tri_state"))
      (node (ref "IC11") (pin "2") (pinfunction "1Q_2") (pintype "tri_state"))
      (node (ref "IC12") (pin "2") (pinfunction "1Q_2") (pintype "tri_state"))
      (node (ref "IC13") (pin "2") (pinfunction "1Q_2") (pintype "tri_state"))
      (node (ref "IC14") (pin "2") (pinfunction "1Q_2") (pintype "tri_state"))
      (node (ref "IC15") (pin "2") (pinfunction "1Q_2") (pintype "tri_state"))
      (node (ref "IC16") (pin "2") (pinfunction "1Q_2") (pintype "tri_state"))
      (node (ref "IC2") (pin "2") (pinfunction "1Q_2") (pintype "tri_state"))
      (node (ref "IC22") (pin "2") (pinfunction "A1_2") (pintype "input"))
      (node (ref "IC3") (pin "2") (pinfunction "1Q_2") (pintype "tri_state"))
      (node (ref "IC4") (pin "2") (pinfunction "1Q_2") (pintype "tri_state"))
      (node (ref "IC5") (pin "2") (pinfunction "1Q_2") (pintype "tri_state"))
      (node (ref "IC6") (pin "2") (pinfunction "1Q_2") (pintype "tri_state"))
      (node (ref "IC7") (pin "2") (pinfunction "1Q_2") (pintype "tri_state"))
      (node (ref "IC8") (pin "2") (pinfunction "1Q_2") (pintype "tri_state"))
      (node (ref "IC9") (pin "2") (pinfunction "1Q_2") (pintype "tri_state"))
    )
    (net (code "53") (name "DATA-OUT1") (class "Default")
      (node (ref "IC1") (pin "5") (pinfunction "2Q_5") (pintype "tri_state"))
      (node (ref "IC10") (pin "5") (pinfunction "2Q_5") (pintype "tri_state"))
      (node (ref "IC11") (pin "5") (pinfunction "2Q_5") (pintype "tri_state"))
      (node (ref "IC12") (pin "5") (pinfunction "2Q_5") (pintype "tri_state"))
      (node (ref "IC13") (pin "5") (pinfunction "2Q_5") (pintype "tri_state"))
      (node (ref "IC14") (pin "5") (pinfunction "2Q_5") (pintype "tri_state"))
      (node (ref "IC15") (pin "5") (pinfunction "2Q_5") (pintype "tri_state"))
      (node (ref "IC16") (pin "5") (pinfunction "2Q_5") (pintype "tri_state"))
      (node (ref "IC2") (pin "5") (pinfunction "2Q_5") (pintype "tri_state"))
      (node (ref "IC22") (pin "4") (pinfunction "A2_4") (pintype "input"))
      (node (ref "IC3") (pin "5") (pinfunction "2Q_5") (pintype "tri_state"))
      (node (ref "IC4") (pin "5") (pinfunction "2Q_5") (pintype "tri_state"))
      (node (ref "IC5") (pin "5") (pinfunction "2Q_5") (pintype "tri_state"))
      (node (ref "IC6") (pin "5") (pinfunction "2Q_5") (pintype "tri_state"))
      (node (ref "IC7") (pin "5") (pinfunction "2Q_5") (pintype "tri_state"))
      (node (ref "IC8") (pin "5") (pinfunction "2Q_5") (pintype "tri_state"))
      (node (ref "IC9") (pin "5") (pinfunction "2Q_5") (pintype "tri_state"))
    )
    (net (code "54") (name "DATA-OUT2") (class "Default")
      (node (ref "IC1") (pin "6") (pinfunction "3Q_6") (pintype "tri_state"))
      (node (ref "IC10") (pin "6") (pinfunction "3Q_6") (pintype "tri_state"))
      (node (ref "IC11") (pin "6") (pinfunction "3Q_6") (pintype "tri_state"))
      (node (ref "IC12") (pin "6") (pinfunction "3Q_6") (pintype "tri_state"))
      (node (ref "IC13") (pin "6") (pinfunction "3Q_6") (pintype "tri_state"))
      (node (ref "IC14") (pin "6") (pinfunction "3Q_6") (pintype "tri_state"))
      (node (ref "IC15") (pin "6") (pinfunction "3Q_6") (pintype "tri_state"))
      (node (ref "IC16") (pin "6") (pinfunction "3Q_6") (pintype "tri_state"))
      (node (ref "IC2") (pin "6") (pinfunction "3Q_6") (pintype "tri_state"))
      (node (ref "IC22") (pin "6") (pinfunction "A3_6") (pintype "input"))
      (node (ref "IC3") (pin "6") (pinfunction "3Q_6") (pintype "tri_state"))
      (node (ref "IC4") (pin "6") (pinfunction "3Q_6") (pintype "tri_state"))
      (node (ref "IC5") (pin "6") (pinfunction "3Q_6") (pintype "tri_state"))
      (node (ref "IC6") (pin "6") (pinfunction "3Q_6") (pintype "tri_state"))
      (node (ref "IC7") (pin "6") (pinfunction "3Q_6") (pintype "tri_state"))
      (node (ref "IC8") (pin "6") (pinfunction "3Q_6") (pintype "tri_state"))
      (node (ref "IC9") (pin "6") (pinfunction "3Q_6") (pintype "tri_state"))
    )
    (net (code "55") (name "DATA-OUT3") (class "Default")
      (node (ref "IC1") (pin "9") (pinfunction "4Q_9") (pintype "tri_state"))
      (node (ref "IC10") (pin "9") (pinfunction "4Q_9") (pintype "tri_state"))
      (node (ref "IC11") (pin "9") (pinfunction "4Q_9") (pintype "tri_state"))
      (node (ref "IC12") (pin "9") (pinfunction "4Q_9") (pintype "tri_state"))
      (node (ref "IC13") (pin "9") (pinfunction "4Q_9") (pintype "tri_state"))
      (node (ref "IC14") (pin "9") (pinfunction "4Q_9") (pintype "tri_state"))
      (node (ref "IC15") (pin "9") (pinfunction "4Q_9") (pintype "tri_state"))
      (node (ref "IC16") (pin "9") (pinfunction "4Q_9") (pintype "tri_state"))
      (node (ref "IC2") (pin "9") (pinfunction "4Q_9") (pintype "tri_state"))
      (node (ref "IC22") (pin "8") (pinfunction "A4_8") (pintype "input"))
      (node (ref "IC3") (pin "9") (pinfunction "4Q_9") (pintype "tri_state"))
      (node (ref "IC4") (pin "9") (pinfunction "4Q_9") (pintype "tri_state"))
      (node (ref "IC5") (pin "9") (pinfunction "4Q_9") (pintype "tri_state"))
      (node (ref "IC6") (pin "9") (pinfunction "4Q_9") (pintype "tri_state"))
      (node (ref "IC7") (pin "9") (pinfunction "4Q_9") (pintype "tri_state"))
      (node (ref "IC8") (pin "9") (pinfunction "4Q_9") (pintype "tri_state"))
      (node (ref "IC9") (pin "9") (pinfunction "4Q_9") (pintype "tri_state"))
    )
    (net (code "56") (name "DATA-OUT4") (class "Default")
      (node (ref "IC1") (pin "12") (pinfunction "5Q_12") (pintype "tri_state"))
      (node (ref "IC10") (pin "12") (pinfunction "5Q_12") (pintype "tri_state"))
      (node (ref "IC11") (pin "12") (pinfunction "5Q_12") (pintype "tri_state"))
      (node (ref "IC12") (pin "12") (pinfunction "5Q_12") (pintype "tri_state"))
      (node (ref "IC13") (pin "12") (pinfunction "5Q_12") (pintype "tri_state"))
      (node (ref "IC14") (pin "12") (pinfunction "5Q_12") (pintype "tri_state"))
      (node (ref "IC15") (pin "12") (pinfunction "5Q_12") (pintype "tri_state"))
      (node (ref "IC16") (pin "12") (pinfunction "5Q_12") (pintype "tri_state"))
      (node (ref "IC2") (pin "12") (pinfunction "5Q_12") (pintype "tri_state"))
      (node (ref "IC22") (pin "11") (pinfunction "A1_11") (pintype "input"))
      (node (ref "IC3") (pin "12") (pinfunction "5Q_12") (pintype "tri_state"))
      (node (ref "IC4") (pin "12") (pinfunction "5Q_12") (pintype "tri_state"))
      (node (ref "IC5") (pin "12") (pinfunction "5Q_12") (pintype "tri_state"))
      (node (ref "IC6") (pin "12") (pinfunction "5Q_12") (pintype "tri_state"))
      (node (ref "IC7") (pin "12") (pinfunction "5Q_12") (pintype "tri_state"))
      (node (ref "IC8") (pin "12") (pinfunction "5Q_12") (pintype "tri_state"))
      (node (ref "IC9") (pin "12") (pinfunction "5Q_12") (pintype "tri_state"))
    )
    (net (code "57") (name "DATA-OUT5") (class "Default")
      (node (ref "IC1") (pin "15") (pinfunction "6Q_15") (pintype "tri_state"))
      (node (ref "IC10") (pin "15") (pinfunction "6Q_15") (pintype "tri_state"))
      (node (ref "IC11") (pin "15") (pinfunction "6Q_15") (pintype "tri_state"))
      (node (ref "IC12") (pin "15") (pinfunction "6Q_15") (pintype "tri_state"))
      (node (ref "IC13") (pin "15") (pinfunction "6Q_15") (pintype "tri_state"))
      (node (ref "IC14") (pin "15") (pinfunction "6Q_15") (pintype "tri_state"))
      (node (ref "IC15") (pin "15") (pinfunction "6Q_15") (pintype "tri_state"))
      (node (ref "IC16") (pin "15") (pinfunction "6Q_15") (pintype "tri_state"))
      (node (ref "IC2") (pin "15") (pinfunction "6Q_15") (pintype "tri_state"))
      (node (ref "IC22") (pin "13") (pinfunction "A2_13") (pintype "input"))
      (node (ref "IC3") (pin "15") (pinfunction "6Q_15") (pintype "tri_state"))
      (node (ref "IC4") (pin "15") (pinfunction "6Q_15") (pintype "tri_state"))
      (node (ref "IC5") (pin "15") (pinfunction "6Q_15") (pintype "tri_state"))
      (node (ref "IC6") (pin "15") (pinfunction "6Q_15") (pintype "tri_state"))
      (node (ref "IC7") (pin "15") (pinfunction "6Q_15") (pintype "tri_state"))
      (node (ref "IC8") (pin "15") (pinfunction "6Q_15") (pintype "tri_state"))
      (node (ref "IC9") (pin "15") (pinfunction "6Q_15") (pintype "tri_state"))
    )
    (net (code "58") (name "DATA-OUT6") (class "Default")
      (node (ref "IC1") (pin "16") (pinfunction "7Q_16") (pintype "tri_state"))
      (node (ref "IC10") (pin "16") (pinfunction "7Q_16") (pintype "tri_state"))
      (node (ref "IC11") (pin "16") (pinfunction "7Q_16") (pintype "tri_state"))
      (node (ref "IC12") (pin "16") (pinfunction "7Q_16") (pintype "tri_state"))
      (node (ref "IC13") (pin "16") (pinfunction "7Q_16") (pintype "tri_state"))
      (node (ref "IC14") (pin "16") (pinfunction "7Q_16") (pintype "tri_state"))
      (node (ref "IC15") (pin "16") (pinfunction "7Q_16") (pintype "tri_state"))
      (node (ref "IC16") (pin "16") (pinfunction "7Q_16") (pintype "tri_state"))
      (node (ref "IC2") (pin "16") (pinfunction "7Q_16") (pintype "tri_state"))
      (node (ref "IC22") (pin "15") (pinfunction "A3_15") (pintype "input"))
      (node (ref "IC3") (pin "16") (pinfunction "7Q_16") (pintype "tri_state"))
      (node (ref "IC4") (pin "16") (pinfunction "7Q_16") (pintype "tri_state"))
      (node (ref "IC5") (pin "16") (pinfunction "7Q_16") (pintype "tri_state"))
      (node (ref "IC6") (pin "16") (pinfunction "7Q_16") (pintype "tri_state"))
      (node (ref "IC7") (pin "16") (pinfunction "7Q_16") (pintype "tri_state"))
      (node (ref "IC8") (pin "16") (pinfunction "7Q_16") (pintype "tri_state"))
      (node (ref "IC9") (pin "16") (pinfunction "7Q_16") (pintype "tri_state"))
    )
    (net (code "59") (name "DATA-OUT7") (class "Default")
      (node (ref "IC1") (pin "19") (pinfunction "8Q_19") (pintype "tri_state"))
      (node (ref "IC10") (pin "19") (pinfunction "8Q_19") (pintype "tri_state"))
      (node (ref "IC11") (pin "19") (pinfunction "8Q_19") (pintype "tri_state"))
      (node (ref "IC12") (pin "19") (pinfunction "8Q_19") (pintype "tri_state"))
      (node (ref "IC13") (pin "19") (pinfunction "8Q_19") (pintype "tri_state"))
      (node (ref "IC14") (pin "19") (pinfunction "8Q_19") (pintype "tri_state"))
      (node (ref "IC15") (pin "19") (pinfunction "8Q_19") (pintype "tri_state"))
      (node (ref "IC16") (pin "19") (pinfunction "8Q_19") (pintype "tri_state"))
      (node (ref "IC2") (pin "19") (pinfunction "8Q_19") (pintype "tri_state"))
      (node (ref "IC22") (pin "17") (pinfunction "A4_17") (pintype "input"))
      (node (ref "IC3") (pin "19") (pinfunction "8Q_19") (pintype "tri_state"))
      (node (ref "IC4") (pin "19") (pinfunction "8Q_19") (pintype "tri_state"))
      (node (ref "IC5") (pin "19") (pinfunction "8Q_19") (pintype "tri_state"))
      (node (ref "IC6") (pin "19") (pinfunction "8Q_19") (pintype "tri_state"))
      (node (ref "IC7") (pin "19") (pinfunction "8Q_19") (pintype "tri_state"))
      (node (ref "IC8") (pin "19") (pinfunction "8Q_19") (pintype "tri_state"))
      (node (ref "IC9") (pin "19") (pinfunction "8Q_19") (pintype "tri_state"))
    )
    (net (code "60") (name "DATA0") (class "Default")
      (node (ref "IC21") (pin "2") (pinfunction "A1_2") (pintype "input"))
      (node (ref "IC22") (pin "18") (pinfunction "Y1_18") (pintype "tri_state"))
      (node (ref "IC46") (pin "2") (pinfunction "A1_2") (pintype "input"))
      (node (ref "IC47") (pin "18") (pinfunction "Y1_18") (pintype "tri_state"))
      (node (ref "X1") (pin "A19") (pinfunction "B_A19") (pintype "passive"))
    )
    (net (code "61") (name "DATA1") (class "Default")
      (node (ref "IC21") (pin "4") (pinfunction "A2_4") (pintype "input"))
      (node (ref "IC22") (pin "16") (pinfunction "Y2_16") (pintype "tri_state"))
      (node (ref "IC46") (pin "4") (pinfunction "A2_4") (pintype "input"))
      (node (ref "IC47") (pin "16") (pinfunction "Y2_16") (pintype "tri_state"))
      (node (ref "X1") (pin "A20") (pinfunction "B_A20") (pintype "passive"))
    )
    (net (code "62") (name "DATA2") (class "Default")
      (node (ref "IC21") (pin "6") (pinfunction "A3_6") (pintype "input"))
      (node (ref "IC22") (pin "14") (pinfunction "Y3_14") (pintype "tri_state"))
      (node (ref "IC46") (pin "6") (pinfunction "A3_6") (pintype "input"))
      (node (ref "IC47") (pin "14") (pinfunction "Y3_14") (pintype "tri_state"))
      (node (ref "X1") (pin "A21") (pinfunction "B_A21") (pintype "passive"))
    )
    (net (code "63") (name "DATA3") (class "Default")
      (node (ref "IC21") (pin "8") (pinfunction "A4_8") (pintype "input"))
      (node (ref "IC22") (pin "12") (pinfunction "Y4_12") (pintype "tri_state"))
      (node (ref "IC46") (pin "8") (pinfunction "A4_8") (pintype "input"))
      (node (ref "IC47") (pin "12") (pinfunction "Y4_12") (pintype "tri_state"))
      (node (ref "X1") (pin "A22") (pinfunction "B_A22") (pintype "passive"))
    )
    (net (code "64") (name "DATA4") (class "Default")
      (node (ref "IC21") (pin "11") (pinfunction "A1_11") (pintype "input"))
      (node (ref "IC22") (pin "9") (pinfunction "Y1_9") (pintype "tri_state"))
      (node (ref "IC46") (pin "11") (pinfunction "A1_11") (pintype "input"))
      (node (ref "IC47") (pin "9") (pinfunction "Y1_9") (pintype "tri_state"))
      (node (ref "X1") (pin "A23") (pinfunction "B_A23") (pintype "passive"))
    )
    (net (code "65") (name "DATA5") (class "Default")
      (node (ref "IC21") (pin "13") (pinfunction "A2_13") (pintype "input"))
      (node (ref "IC22") (pin "7") (pinfunction "Y2_7") (pintype "tri_state"))
      (node (ref "IC46") (pin "13") (pinfunction "A2_13") (pintype "input"))
      (node (ref "IC47") (pin "7") (pinfunction "Y2_7") (pintype "tri_state"))
      (node (ref "X1") (pin "A24") (pinfunction "B_A24") (pintype "passive"))
    )
    (net (code "66") (name "DATA6") (class "Default")
      (node (ref "IC21") (pin "15") (pinfunction "A3_15") (pintype "input"))
      (node (ref "IC22") (pin "5") (pinfunction "Y3_5") (pintype "tri_state"))
      (node (ref "IC46") (pin "15") (pinfunction "A3_15") (pintype "input"))
      (node (ref "IC47") (pin "5") (pinfunction "Y3_5") (pintype "tri_state"))
      (node (ref "X1") (pin "A25") (pinfunction "B_A25") (pintype "passive"))
    )
    (net (code "67") (name "DATA7") (class "Default")
      (node (ref "IC21") (pin "17") (pinfunction "A4_17") (pintype "input"))
      (node (ref "IC22") (pin "3") (pinfunction "Y4_3") (pintype "tri_state"))
      (node (ref "IC46") (pin "17") (pinfunction "A4_17") (pintype "input"))
      (node (ref "IC47") (pin "3") (pinfunction "Y4_3") (pintype "tri_state"))
      (node (ref "X1") (pin "A26") (pinfunction "B_A26") (pintype "passive"))
    )
    (net (code "68") (name "DATA8") (class "Default")
      (node (ref "X1") (pin "A27") (pinfunction "B_A27") (pintype "passive"))
    )
    (net (code "69") (name "DATA9") (class "Default")
      (node (ref "X1") (pin "A28") (pinfunction "B_A28") (pintype "passive"))
    )
    (net (code "70") (name "DATA10") (class "Default")
      (node (ref "X1") (pin "A29") (pinfunction "B_A29") (pintype "passive"))
    )
    (net (code "71") (name "DATA11") (class "Default")
      (node (ref "X1") (pin "A30") (pinfunction "B_A30") (pintype "passive"))
    )
    (net (code "72") (name "DATA12") (class "Default")
      (node (ref "X1") (pin "B3") (pinfunction "B_B3") (pintype "passive"))
    )
    (net (code "73") (name "DATA13") (class "Default")
      (node (ref "X1") (pin "B4") (pinfunction "B_B4") (pintype "passive"))
    )
    (net (code "74") (name "DATA14") (class "Default")
      (node (ref "X1") (pin "B5") (pinfunction "B_B5") (pintype "passive"))
    )
    (net (code "75") (name "DATA15") (class "Default")
      (node (ref "X1") (pin "B6") (pinfunction "B_B6") (pintype "passive"))
    )
    (net (code "76") (name "DATAB-IN0") (class "Default")
      (node (ref "IC26") (pin "3") (pinfunction "1D_3") (pintype "input"))
      (node (ref "IC27") (pin "3") (pinfunction "1D_3") (pintype "input"))
      (node (ref "IC28") (pin "3") (pinfunction "1D_3") (pintype "input"))
      (node (ref "IC29") (pin "3") (pinfunction "1D_3") (pintype "input"))
      (node (ref "IC30") (pin "3") (pinfunction "1D_3") (pintype "input"))
      (node (ref "IC31") (pin "3") (pinfunction "1D_3") (pintype "input"))
      (node (ref "IC32") (pin "3") (pinfunction "1D_3") (pintype "input"))
      (node (ref "IC33") (pin "3") (pinfunction "1D_3") (pintype "input"))
      (node (ref "IC34") (pin "3") (pinfunction "1D_3") (pintype "input"))
      (node (ref "IC35") (pin "3") (pinfunction "1D_3") (pintype "input"))
      (node (ref "IC36") (pin "3") (pinfunction "1D_3") (pintype "input"))
      (node (ref "IC37") (pin "3") (pinfunction "1D_3") (pintype "input"))
      (node (ref "IC38") (pin "3") (pinfunction "1D_3") (pintype "input"))
      (node (ref "IC39") (pin "3") (pinfunction "1D_3") (pintype "input"))
      (node (ref "IC40") (pin "3") (pinfunction "1D_3") (pintype "input"))
      (node (ref "IC41") (pin "3") (pinfunction "1D_3") (pintype "input"))
      (node (ref "IC46") (pin "18") (pinfunction "Y1_18") (pintype "tri_state"))
    )
    (net (code "77") (name "DATAB-IN1") (class "Default")
      (node (ref "IC26") (pin "4") (pinfunction "2D_4") (pintype "input"))
      (node (ref "IC27") (pin "4") (pinfunction "2D_4") (pintype "input"))
      (node (ref "IC28") (pin "4") (pinfunction "2D_4") (pintype "input"))
      (node (ref "IC29") (pin "4") (pinfunction "2D_4") (pintype "input"))
      (node (ref "IC30") (pin "4") (pinfunction "2D_4") (pintype "input"))
      (node (ref "IC31") (pin "4") (pinfunction "2D_4") (pintype "input"))
      (node (ref "IC32") (pin "4") (pinfunction "2D_4") (pintype "input"))
      (node (ref "IC33") (pin "4") (pinfunction "2D_4") (pintype "input"))
      (node (ref "IC34") (pin "4") (pinfunction "2D_4") (pintype "input"))
      (node (ref "IC35") (pin "4") (pinfunction "2D_4") (pintype "input"))
      (node (ref "IC36") (pin "4") (pinfunction "2D_4") (pintype "input"))
      (node (ref "IC37") (pin "4") (pinfunction "2D_4") (pintype "input"))
      (node (ref "IC38") (pin "4") (pinfunction "2D_4") (pintype "input"))
      (node (ref "IC39") (pin "4") (pinfunction "2D_4") (pintype "input"))
      (node (ref "IC40") (pin "4") (pinfunction "2D_4") (pintype "input"))
      (node (ref "IC41") (pin "4") (pinfunction "2D_4") (pintype "input"))
      (node (ref "IC46") (pin "16") (pinfunction "Y2_16") (pintype "tri_state"))
    )
    (net (code "78") (name "DATAB-IN2") (class "Default")
      (node (ref "IC26") (pin "7") (pinfunction "3D_7") (pintype "input"))
      (node (ref "IC27") (pin "7") (pinfunction "3D_7") (pintype "input"))
      (node (ref "IC28") (pin "7") (pinfunction "3D_7") (pintype "input"))
      (node (ref "IC29") (pin "7") (pinfunction "3D_7") (pintype "input"))
      (node (ref "IC30") (pin "7") (pinfunction "3D_7") (pintype "input"))
      (node (ref "IC31") (pin "7") (pinfunction "3D_7") (pintype "input"))
      (node (ref "IC32") (pin "7") (pinfunction "3D_7") (pintype "input"))
      (node (ref "IC33") (pin "7") (pinfunction "3D_7") (pintype "input"))
      (node (ref "IC34") (pin "7") (pinfunction "3D_7") (pintype "input"))
      (node (ref "IC35") (pin "7") (pinfunction "3D_7") (pintype "input"))
      (node (ref "IC36") (pin "7") (pinfunction "3D_7") (pintype "input"))
      (node (ref "IC37") (pin "7") (pinfunction "3D_7") (pintype "input"))
      (node (ref "IC38") (pin "7") (pinfunction "3D_7") (pintype "input"))
      (node (ref "IC39") (pin "7") (pinfunction "3D_7") (pintype "input"))
      (node (ref "IC40") (pin "7") (pinfunction "3D_7") (pintype "input"))
      (node (ref "IC41") (pin "7") (pinfunction "3D_7") (pintype "input"))
      (node (ref "IC46") (pin "14") (pinfunction "Y3_14") (pintype "tri_state"))
    )
    (net (code "79") (name "DATAB-IN3") (class "Default")
      (node (ref "IC26") (pin "8") (pinfunction "4D_8") (pintype "input"))
      (node (ref "IC27") (pin "8") (pinfunction "4D_8") (pintype "input"))
      (node (ref "IC28") (pin "8") (pinfunction "4D_8") (pintype "input"))
      (node (ref "IC29") (pin "8") (pinfunction "4D_8") (pintype "input"))
      (node (ref "IC30") (pin "8") (pinfunction "4D_8") (pintype "input"))
      (node (ref "IC31") (pin "8") (pinfunction "4D_8") (pintype "input"))
      (node (ref "IC32") (pin "8") (pinfunction "4D_8") (pintype "input"))
      (node (ref "IC33") (pin "8") (pinfunction "4D_8") (pintype "input"))
      (node (ref "IC34") (pin "8") (pinfunction "4D_8") (pintype "input"))
      (node (ref "IC35") (pin "8") (pinfunction "4D_8") (pintype "input"))
      (node (ref "IC36") (pin "8") (pinfunction "4D_8") (pintype "input"))
      (node (ref "IC37") (pin "8") (pinfunction "4D_8") (pintype "input"))
      (node (ref "IC38") (pin "8") (pinfunction "4D_8") (pintype "input"))
      (node (ref "IC39") (pin "8") (pinfunction "4D_8") (pintype "input"))
      (node (ref "IC40") (pin "8") (pinfunction "4D_8") (pintype "input"))
      (node (ref "IC41") (pin "8") (pinfunction "4D_8") (pintype "input"))
      (node (ref "IC46") (pin "12") (pinfunction "Y4_12") (pintype "tri_state"))
    )
    (net (code "80") (name "DATAB-IN4") (class "Default")
      (node (ref "IC26") (pin "13") (pinfunction "5D_13") (pintype "input"))
      (node (ref "IC27") (pin "13") (pinfunction "5D_13") (pintype "input"))
      (node (ref "IC28") (pin "13") (pinfunction "5D_13") (pintype "input"))
      (node (ref "IC29") (pin "13") (pinfunction "5D_13") (pintype "input"))
      (node (ref "IC30") (pin "13") (pinfunction "5D_13") (pintype "input"))
      (node (ref "IC31") (pin "13") (pinfunction "5D_13") (pintype "input"))
      (node (ref "IC32") (pin "13") (pinfunction "5D_13") (pintype "input"))
      (node (ref "IC33") (pin "13") (pinfunction "5D_13") (pintype "input"))
      (node (ref "IC34") (pin "13") (pinfunction "5D_13") (pintype "input"))
      (node (ref "IC35") (pin "13") (pinfunction "5D_13") (pintype "input"))
      (node (ref "IC36") (pin "13") (pinfunction "5D_13") (pintype "input"))
      (node (ref "IC37") (pin "13") (pinfunction "5D_13") (pintype "input"))
      (node (ref "IC38") (pin "13") (pinfunction "5D_13") (pintype "input"))
      (node (ref "IC39") (pin "13") (pinfunction "5D_13") (pintype "input"))
      (node (ref "IC40") (pin "13") (pinfunction "5D_13") (pintype "input"))
      (node (ref "IC41") (pin "13") (pinfunction "5D_13") (pintype "input"))
      (node (ref "IC46") (pin "9") (pinfunction "Y1_9") (pintype "tri_state"))
    )
    (net (code "81") (name "DATAB-IN5") (class "Default")
      (node (ref "IC26") (pin "14") (pinfunction "6D_14") (pintype "input"))
      (node (ref "IC27") (pin "14") (pinfunction "6D_14") (pintype "input"))
      (node (ref "IC28") (pin "14") (pinfunction "6D_14") (pintype "input"))
      (node (ref "IC29") (pin "14") (pinfunction "6D_14") (pintype "input"))
      (node (ref "IC30") (pin "14") (pinfunction "6D_14") (pintype "input"))
      (node (ref "IC31") (pin "14") (pinfunction "6D_14") (pintype "input"))
      (node (ref "IC32") (pin "14") (pinfunction "6D_14") (pintype "input"))
      (node (ref "IC33") (pin "14") (pinfunction "6D_14") (pintype "input"))
      (node (ref "IC34") (pin "14") (pinfunction "6D_14") (pintype "input"))
      (node (ref "IC35") (pin "14") (pinfunction "6D_14") (pintype "input"))
      (node (ref "IC36") (pin "14") (pinfunction "6D_14") (pintype "input"))
      (node (ref "IC37") (pin "14") (pinfunction "6D_14") (pintype "input"))
      (node (ref "IC38") (pin "14") (pinfunction "6D_14") (pintype "input"))
      (node (ref "IC39") (pin "14") (pinfunction "6D_14") (pintype "input"))
      (node (ref "IC40") (pin "14") (pinfunction "6D_14") (pintype "input"))
      (node (ref "IC41") (pin "14") (pinfunction "6D_14") (pintype "input"))
      (node (ref "IC46") (pin "7") (pinfunction "Y2_7") (pintype "tri_state"))
    )
    (net (code "82") (name "DATAB-IN6") (class "Default")
      (node (ref "IC26") (pin "17") (pinfunction "7D_17") (pintype "input"))
      (node (ref "IC27") (pin "17") (pinfunction "7D_17") (pintype "input"))
      (node (ref "IC28") (pin "17") (pinfunction "7D_17") (pintype "input"))
      (node (ref "IC29") (pin "17") (pinfunction "7D_17") (pintype "input"))
      (node (ref "IC30") (pin "17") (pinfunction "7D_17") (pintype "input"))
      (node (ref "IC31") (pin "17") (pinfunction "7D_17") (pintype "input"))
      (node (ref "IC32") (pin "17") (pinfunction "7D_17") (pintype "input"))
      (node (ref "IC33") (pin "17") (pinfunction "7D_17") (pintype "input"))
      (node (ref "IC34") (pin "17") (pinfunction "7D_17") (pintype "input"))
      (node (ref "IC35") (pin "17") (pinfunction "7D_17") (pintype "input"))
      (node (ref "IC36") (pin "17") (pinfunction "7D_17") (pintype "input"))
      (node (ref "IC37") (pin "17") (pinfunction "7D_17") (pintype "input"))
      (node (ref "IC38") (pin "17") (pinfunction "7D_17") (pintype "input"))
      (node (ref "IC39") (pin "17") (pinfunction "7D_17") (pintype "input"))
      (node (ref "IC40") (pin "17") (pinfunction "7D_17") (pintype "input"))
      (node (ref "IC41") (pin "17") (pinfunction "7D_17") (pintype "input"))
      (node (ref "IC46") (pin "5") (pinfunction "Y3_5") (pintype "tri_state"))
    )
    (net (code "83") (name "DATAB-IN7") (class "Default")
      (node (ref "IC26") (pin "18") (pinfunction "8D_18") (pintype "input"))
      (node (ref "IC27") (pin "18") (pinfunction "8D_18") (pintype "input"))
      (node (ref "IC28") (pin "18") (pinfunction "8D_18") (pintype "input"))
      (node (ref "IC29") (pin "18") (pinfunction "8D_18") (pintype "input"))
      (node (ref "IC30") (pin "18") (pinfunction "8D_18") (pintype "input"))
      (node (ref "IC31") (pin "18") (pinfunction "8D_18") (pintype "input"))
      (node (ref "IC32") (pin "18") (pinfunction "8D_18") (pintype "input"))
      (node (ref "IC33") (pin "18") (pinfunction "8D_18") (pintype "input"))
      (node (ref "IC34") (pin "18") (pinfunction "8D_18") (pintype "input"))
      (node (ref "IC35") (pin "18") (pinfunction "8D_18") (pintype "input"))
      (node (ref "IC36") (pin "18") (pinfunction "8D_18") (pintype "input"))
      (node (ref "IC37") (pin "18") (pinfunction "8D_18") (pintype "input"))
      (node (ref "IC38") (pin "18") (pinfunction "8D_18") (pintype "input"))
      (node (ref "IC39") (pin "18") (pinfunction "8D_18") (pintype "input"))
      (node (ref "IC40") (pin "18") (pinfunction "8D_18") (pintype "input"))
      (node (ref "IC41") (pin "18") (pinfunction "8D_18") (pintype "input"))
      (node (ref "IC46") (pin "3") (pinfunction "Y4_3") (pintype "tri_state"))
    )
    (net (code "84") (name "DATAB-OUT0") (class "Default")
      (node (ref "IC26") (pin "2") (pinfunction "1Q_2") (pintype "tri_state"))
      (node (ref "IC27") (pin "2") (pinfunction "1Q_2") (pintype "tri_state"))
      (node (ref "IC28") (pin "2") (pinfunction "1Q_2") (pintype "tri_state"))
      (node (ref "IC29") (pin "2") (pinfunction "1Q_2") (pintype "tri_state"))
      (node (ref "IC30") (pin "2") (pinfunction "1Q_2") (pintype "tri_state"))
      (node (ref "IC31") (pin "2") (pinfunction "1Q_2") (pintype "tri_state"))
      (node (ref "IC32") (pin "2") (pinfunction "1Q_2") (pintype "tri_state"))
      (node (ref "IC33") (pin "2") (pinfunction "1Q_2") (pintype "tri_state"))
      (node (ref "IC34") (pin "2") (pinfunction "1Q_2") (pintype "tri_state"))
      (node (ref "IC35") (pin "2") (pinfunction "1Q_2") (pintype "tri_state"))
      (node (ref "IC36") (pin "2") (pinfunction "1Q_2") (pintype "tri_state"))
      (node (ref "IC37") (pin "2") (pinfunction "1Q_2") (pintype "tri_state"))
      (node (ref "IC38") (pin "2") (pinfunction "1Q_2") (pintype "tri_state"))
      (node (ref "IC39") (pin "2") (pinfunction "1Q_2") (pintype "tri_state"))
      (node (ref "IC40") (pin "2") (pinfunction "1Q_2") (pintype "tri_state"))
      (node (ref "IC41") (pin "2") (pinfunction "1Q_2") (pintype "tri_state"))
      (node (ref "IC47") (pin "2") (pinfunction "A1_2") (pintype "input"))
    )
    (net (code "85") (name "DATAB-OUT1") (class "Default")
      (node (ref "IC26") (pin "5") (pinfunction "2Q_5") (pintype "tri_state"))
      (node (ref "IC27") (pin "5") (pinfunction "2Q_5") (pintype "tri_state"))
      (node (ref "IC28") (pin "5") (pinfunction "2Q_5") (pintype "tri_state"))
      (node (ref "IC29") (pin "5") (pinfunction "2Q_5") (pintype "tri_state"))
      (node (ref "IC30") (pin "5") (pinfunction "2Q_5") (pintype "tri_state"))
      (node (ref "IC31") (pin "5") (pinfunction "2Q_5") (pintype "tri_state"))
      (node (ref "IC32") (pin "5") (pinfunction "2Q_5") (pintype "tri_state"))
      (node (ref "IC33") (pin "5") (pinfunction "2Q_5") (pintype "tri_state"))
      (node (ref "IC34") (pin "5") (pinfunction "2Q_5") (pintype "tri_state"))
      (node (ref "IC35") (pin "5") (pinfunction "2Q_5") (pintype "tri_state"))
      (node (ref "IC36") (pin "5") (pinfunction "2Q_5") (pintype "tri_state"))
      (node (ref "IC37") (pin "5") (pinfunction "2Q_5") (pintype "tri_state"))
      (node (ref "IC38") (pin "5") (pinfunction "2Q_5") (pintype "tri_state"))
      (node (ref "IC39") (pin "5") (pinfunction "2Q_5") (pintype "tri_state"))
      (node (ref "IC40") (pin "5") (pinfunction "2Q_5") (pintype "tri_state"))
      (node (ref "IC41") (pin "5") (pinfunction "2Q_5") (pintype "tri_state"))
      (node (ref "IC47") (pin "4") (pinfunction "A2_4") (pintype "input"))
    )
    (net (code "86") (name "DATAB-OUT2") (class "Default")
      (node (ref "IC26") (pin "6") (pinfunction "3Q_6") (pintype "tri_state"))
      (node (ref "IC27") (pin "6") (pinfunction "3Q_6") (pintype "tri_state"))
      (node (ref "IC28") (pin "6") (pinfunction "3Q_6") (pintype "tri_state"))
      (node (ref "IC29") (pin "6") (pinfunction "3Q_6") (pintype "tri_state"))
      (node (ref "IC30") (pin "6") (pinfunction "3Q_6") (pintype "tri_state"))
      (node (ref "IC31") (pin "6") (pinfunction "3Q_6") (pintype "tri_state"))
      (node (ref "IC32") (pin "6") (pinfunction "3Q_6") (pintype "tri_state"))
      (node (ref "IC33") (pin "6") (pinfunction "3Q_6") (pintype "tri_state"))
      (node (ref "IC34") (pin "6") (pinfunction "3Q_6") (pintype "tri_state"))
      (node (ref "IC35") (pin "6") (pinfunction "3Q_6") (pintype "tri_state"))
      (node (ref "IC36") (pin "6") (pinfunction "3Q_6") (pintype "tri_state"))
      (node (ref "IC37") (pin "6") (pinfunction "3Q_6") (pintype "tri_state"))
      (node (ref "IC38") (pin "6") (pinfunction "3Q_6") (pintype "tri_state"))
      (node (ref "IC39") (pin "6") (pinfunction "3Q_6") (pintype "tri_state"))
      (node (ref "IC40") (pin "6") (pinfunction "3Q_6") (pintype "tri_state"))
      (node (ref "IC41") (pin "6") (pinfunction "3Q_6") (pintype "tri_state"))
      (node (ref "IC47") (pin "6") (pinfunction "A3_6") (pintype "input"))
    )
    (net (code "87") (name "DATAB-OUT3") (class "Default")
      (node (ref "IC26") (pin "9") (pinfunction "4Q_9") (pintype "tri_state"))
      (node (ref "IC27") (pin "9") (pinfunction "4Q_9") (pintype "tri_state"))
      (node (ref "IC28") (pin "9") (pinfunction "4Q_9") (pintype "tri_state"))
      (node (ref "IC29") (pin "9") (pinfunction "4Q_9") (pintype "tri_state"))
      (node (ref "IC30") (pin "9") (pinfunction "4Q_9") (pintype "tri_state"))
      (node (ref "IC31") (pin "9") (pinfunction "4Q_9") (pintype "tri_state"))
      (node (ref "IC32") (pin "9") (pinfunction "4Q_9") (pintype "tri_state"))
      (node (ref "IC33") (pin "9") (pinfunction "4Q_9") (pintype "tri_state"))
      (node (ref "IC34") (pin "9") (pinfunction "4Q_9") (pintype "tri_state"))
      (node (ref "IC35") (pin "9") (pinfunction "4Q_9") (pintype "tri_state"))
      (node (ref "IC36") (pin "9") (pinfunction "4Q_9") (pintype "tri_state"))
      (node (ref "IC37") (pin "9") (pinfunction "4Q_9") (pintype "tri_state"))
      (node (ref "IC38") (pin "9") (pinfunction "4Q_9") (pintype "tri_state"))
      (node (ref "IC39") (pin "9") (pinfunction "4Q_9") (pintype "tri_state"))
      (node (ref "IC40") (pin "9") (pinfunction "4Q_9") (pintype "tri_state"))
      (node (ref "IC41") (pin "9") (pinfunction "4Q_9") (pintype "tri_state"))
      (node (ref "IC47") (pin "8") (pinfunction "A4_8") (pintype "input"))
    )
    (net (code "88") (name "DATAB-OUT4") (class "Default")
      (node (ref "IC26") (pin "12") (pinfunction "5Q_12") (pintype "tri_state"))
      (node (ref "IC27") (pin "12") (pinfunction "5Q_12") (pintype "tri_state"))
      (node (ref "IC28") (pin "12") (pinfunction "5Q_12") (pintype "tri_state"))
      (node (ref "IC29") (pin "12") (pinfunction "5Q_12") (pintype "tri_state"))
      (node (ref "IC30") (pin "12") (pinfunction "5Q_12") (pintype "tri_state"))
      (node (ref "IC31") (pin "12") (pinfunction "5Q_12") (pintype "tri_state"))
      (node (ref "IC32") (pin "12") (pinfunction "5Q_12") (pintype "tri_state"))
      (node (ref "IC33") (pin "12") (pinfunction "5Q_12") (pintype "tri_state"))
      (node (ref "IC34") (pin "12") (pinfunction "5Q_12") (pintype "tri_state"))
      (node (ref "IC35") (pin "12") (pinfunction "5Q_12") (pintype "tri_state"))
      (node (ref "IC36") (pin "12") (pinfunction "5Q_12") (pintype "tri_state"))
      (node (ref "IC37") (pin "12") (pinfunction "5Q_12") (pintype "tri_state"))
      (node (ref "IC38") (pin "12") (pinfunction "5Q_12") (pintype "tri_state"))
      (node (ref "IC39") (pin "12") (pinfunction "5Q_12") (pintype "tri_state"))
      (node (ref "IC40") (pin "12") (pinfunction "5Q_12") (pintype "tri_state"))
      (node (ref "IC41") (pin "12") (pinfunction "5Q_12") (pintype "tri_state"))
      (node (ref "IC47") (pin "11") (pinfunction "A1_11") (pintype "input"))
    )
    (net (code "89") (name "DATAB-OUT5") (class "Default")
      (node (ref "IC26") (pin "15") (pinfunction "6Q_15") (pintype "tri_state"))
      (node (ref "IC27") (pin "15") (pinfunction "6Q_15") (pintype "tri_state"))
      (node (ref "IC28") (pin "15") (pinfunction "6Q_15") (pintype "tri_state"))
      (node (ref "IC29") (pin "15") (pinfunction "6Q_15") (pintype "tri_state"))
      (node (ref "IC30") (pin "15") (pinfunction "6Q_15") (pintype "tri_state"))
      (node (ref "IC31") (pin "15") (pinfunction "6Q_15") (pintype "tri_state"))
      (node (ref "IC32") (pin "15") (pinfunction "6Q_15") (pintype "tri_state"))
      (node (ref "IC33") (pin "15") (pinfunction "6Q_15") (pintype "tri_state"))
      (node (ref "IC34") (pin "15") (pinfunction "6Q_15") (pintype "tri_state"))
      (node (ref "IC35") (pin "15") (pinfunction "6Q_15") (pintype "tri_state"))
      (node (ref "IC36") (pin "15") (pinfunction "6Q_15") (pintype "tri_state"))
      (node (ref "IC37") (pin "15") (pinfunction "6Q_15") (pintype "tri_state"))
      (node (ref "IC38") (pin "15") (pinfunction "6Q_15") (pintype "tri_state"))
      (node (ref "IC39") (pin "15") (pinfunction "6Q_15") (pintype "tri_state"))
      (node (ref "IC40") (pin "15") (pinfunction "6Q_15") (pintype "tri_state"))
      (node (ref "IC41") (pin "15") (pinfunction "6Q_15") (pintype "tri_state"))
      (node (ref "IC47") (pin "13") (pinfunction "A2_13") (pintype "input"))
    )
    (net (code "90") (name "DATAB-OUT6") (class "Default")
      (node (ref "IC26") (pin "16") (pinfunction "7Q_16") (pintype "tri_state"))
      (node (ref "IC27") (pin "16") (pinfunction "7Q_16") (pintype "tri_state"))
      (node (ref "IC28") (pin "16") (pinfunction "7Q_16") (pintype "tri_state"))
      (node (ref "IC29") (pin "16") (pinfunction "7Q_16") (pintype "tri_state"))
      (node (ref "IC30") (pin "16") (pinfunction "7Q_16") (pintype "tri_state"))
      (node (ref "IC31") (pin "16") (pinfunction "7Q_16") (pintype "tri_state"))
      (node (ref "IC32") (pin "16") (pinfunction "7Q_16") (pintype "tri_state"))
      (node (ref "IC33") (pin "16") (pinfunction "7Q_16") (pintype "tri_state"))
      (node (ref "IC34") (pin "16") (pinfunction "7Q_16") (pintype "tri_state"))
      (node (ref "IC35") (pin "16") (pinfunction "7Q_16") (pintype "tri_state"))
      (node (ref "IC36") (pin "16") (pinfunction "7Q_16") (pintype "tri_state"))
      (node (ref "IC37") (pin "16") (pinfunction "7Q_16") (pintype "tri_state"))
      (node (ref "IC38") (pin "16") (pinfunction "7Q_16") (pintype "tri_state"))
      (node (ref "IC39") (pin "16") (pinfunction "7Q_16") (pintype "tri_state"))
      (node (ref "IC40") (pin "16") (pinfunction "7Q_16") (pintype "tri_state"))
      (node (ref "IC41") (pin "16") (pinfunction "7Q_16") (pintype "tri_state"))
      (node (ref "IC47") (pin "15") (pinfunction "A3_15") (pintype "input"))
    )
    (net (code "91") (name "DATAB-OUT7") (class "Default")
      (node (ref "IC26") (pin "19") (pinfunction "8Q_19") (pintype "tri_state"))
      (node (ref "IC27") (pin "19") (pinfunction "8Q_19") (pintype "tri_state"))
      (node (ref "IC28") (pin "19") (pinfunction "8Q_19") (pintype "tri_state"))
      (node (ref "IC29") (pin "19") (pinfunction "8Q_19") (pintype "tri_state"))
      (node (ref "IC30") (pin "19") (pinfunction "8Q_19") (pintype "tri_state"))
      (node (ref "IC31") (pin "19") (pinfunction "8Q_19") (pintype "tri_state"))
      (node (ref "IC32") (pin "19") (pinfunction "8Q_19") (pintype "tri_state"))
      (node (ref "IC33") (pin "19") (pinfunction "8Q_19") (pintype "tri_state"))
      (node (ref "IC34") (pin "19") (pinfunction "8Q_19") (pintype "tri_state"))
      (node (ref "IC35") (pin "19") (pinfunction "8Q_19") (pintype "tri_state"))
      (node (ref "IC36") (pin "19") (pinfunction "8Q_19") (pintype "tri_state"))
      (node (ref "IC37") (pin "19") (pinfunction "8Q_19") (pintype "tri_state"))
      (node (ref "IC38") (pin "19") (pinfunction "8Q_19") (pintype "tri_state"))
      (node (ref "IC39") (pin "19") (pinfunction "8Q_19") (pintype "tri_state"))
      (node (ref "IC40") (pin "19") (pinfunction "8Q_19") (pintype "tri_state"))
      (node (ref "IC41") (pin "19") (pinfunction "8Q_19") (pintype "tri_state"))
      (node (ref "IC47") (pin "17") (pinfunction "A4_17") (pintype "input"))
    )
    (net (code "92") (name "GND") (class "Default")
      (node (ref "IC21") (pin "1") (pinfunction "G_1") (pintype "input"))
      (node (ref "IC21") (pin "19") (pinfunction "G_19") (pintype "input"))
      (node (ref "IC23") (pin "10") (pinfunction "I1_10") (pintype "input"))
      (node (ref "IC23") (pin "4") (pinfunction "I0_4") (pintype "input"))
      (node (ref "IC23") (pin "5") (pinfunction "I1_5") (pintype "input"))
      (node (ref "IC23") (pin "9") (pinfunction "I0_9") (pintype "input"))
      (node (ref "IC24") (pin "11") (pinfunction "I_11") (pintype "input"))
      (node (ref "IC24") (pin "13") (pinfunction "I_13") (pintype "input"))
      (node (ref "IC46") (pin "1") (pinfunction "G_1") (pintype "input"))
      (node (ref "IC46") (pin "19") (pinfunction "G_19") (pintype "input"))
      (node (ref "PWR") (pin "K") (pinfunction "C_K") (pintype "passive"))
      (node (ref "X1") (pin "A1") (pinfunction "B_A1") (pintype "passive"))
      (node (ref "X1") (pin "A32") (pinfunction "B_A32") (pintype "passive"))
      (node (ref "X1") (pin "B1") (pinfunction "B_B1") (pintype "passive"))
      (node (ref "X1") (pin "B32") (pinfunction "B_B32") (pintype "passive"))
      (node (ref "X1") (pin "C1") (pinfunction "B_C1") (pintype "passive"))
      (node (ref "X1") (pin "C32") (pinfunction "B_C32") (pintype "passive"))
    )
    (net (code "93") (name "H{slash}L-SWAP") (class "Default")
      (node (ref "X1") (pin "C25") (pinfunction "B_C25") (pintype "passive"))
    )
    (net (code "94") (name "IN") (class "Default")
      (node (ref "X1") (pin "C26") (pinfunction "B_C26") (pintype "passive"))
    )
    (net (code "95") (name "INT") (class "Default")
      (node (ref "X1") (pin "B29") (pinfunction "B_B29") (pintype "passive"))
    )
    (net (code "96") (name "INTA") (class "Default")
      (node (ref "X1") (pin "B30") (pinfunction "B_B30") (pintype "passive"))
    )
    (net (code "97") (name "I{slash}O-ADDR") (class "Default")
      (node (ref "X1") (pin "B28") (pinfunction "B_B28") (pintype "passive"))
    )
    (net (code "98") (name "I{slash}O-RD") (class "Default")
      (node (ref "X1") (pin "B27") (pinfunction "B_B27") (pintype "passive"))
    )
    (net (code "99") (name "I{slash}O-WR") (class "Default")
      (node (ref "X1") (pin "B26") (pinfunction "B_B26") (pintype "passive"))
    )
    (net (code "100") (name "MEM-RD") (class "Default")
      (node (ref "IC24") (pin "3") (pinfunction "I_3") (pintype "input"))
      (node (ref "X1") (pin "B25") (pinfunction "B_B25") (pintype "passive"))
    )
    (net (code "101") (name "MEM-WR") (class "Default")
      (node (ref "IC24") (pin "5") (pinfunction "I_5") (pintype "input"))
      (node (ref "X1") (pin "B24") (pinfunction "B_B24") (pintype "passive"))
    )
    (net (code "102") (name "MEM0-LD") (class "Default")
      (node (ref "IC1") (pin "11") (pinfunction "CLK_11") (pintype "input"))
      (node (ref "IC19") (pin "15") (pinfunction "Y0_15") (pintype "output"))
    )
    (net (code "103") (name "MEM0-RD") (class "Default")
      (node (ref "IC1") (pin "1") (pinfunction "OC_1") (pintype "input"))
      (node (ref "IC17") (pin "15") (pinfunction "Y0_15") (pintype "output"))
    )
    (net (code "104") (name "MEM0B-LD") (class "Default")
      (node (ref "IC26") (pin "11") (pinfunction "CLK_11") (pintype "input"))
      (node (ref "IC44") (pin "15") (pinfunction "Y0_15") (pintype "output"))
    )
    (net (code "105") (name "MEM0B-RD") (class "Default")
      (node (ref "IC26") (pin "1") (pinfunction "OC_1") (pintype "input"))
      (node (ref "IC42") (pin "15") (pinfunction "Y0_15") (pintype "output"))
    )
    (net (code "106") (name "MEM1-LD") (class "Default")
      (node (ref "IC19") (pin "14") (pinfunction "Y1_14") (pintype "output"))
      (node (ref "IC2") (pin "11") (pinfunction "CLK_11") (pintype "input"))
    )
    (net (code "107") (name "MEM1-RD") (class "Default")
      (node (ref "IC17") (pin "14") (pinfunction "Y1_14") (pintype "output"))
      (node (ref "IC2") (pin "1") (pinfunction "OC_1") (pintype "input"))
    )
    (net (code "108") (name "MEM1B-LD") (class "Default")
      (node (ref "IC27") (pin "11") (pinfunction "CLK_11") (pintype "input"))
      (node (ref "IC44") (pin "14") (pinfunction "Y1_14") (pintype "output"))
    )
    (net (code "109") (name "MEM1B-RD") (class "Default")
      (node (ref "IC27") (pin "1") (pinfunction "OC_1") (pintype "input"))
      (node (ref "IC42") (pin "14") (pinfunction "Y1_14") (pintype "output"))
    )
    (net (code "110") (name "MEM2-LD") (class "Default")
      (node (ref "IC19") (pin "13") (pinfunction "Y2_13") (pintype "output"))
      (node (ref "IC3") (pin "11") (pinfunction "CLK_11") (pintype "input"))
    )
    (net (code "111") (name "MEM2-RD") (class "Default")
      (node (ref "IC17") (pin "13") (pinfunction "Y2_13") (pintype "output"))
      (node (ref "IC3") (pin "1") (pinfunction "OC_1") (pintype "input"))
    )
    (net (code "112") (name "MEM2B-LD") (class "Default")
      (node (ref "IC28") (pin "11") (pinfunction "CLK_11") (pintype "input"))
      (node (ref "IC44") (pin "13") (pinfunction "Y2_13") (pintype "output"))
    )
    (net (code "113") (name "MEM2B-RD") (class "Default")
      (node (ref "IC28") (pin "1") (pinfunction "OC_1") (pintype "input"))
      (node (ref "IC42") (pin "13") (pinfunction "Y2_13") (pintype "output"))
    )
    (net (code "114") (name "MEM3-LD") (class "Default")
      (node (ref "IC19") (pin "12") (pinfunction "Y3_12") (pintype "output"))
      (node (ref "IC4") (pin "11") (pinfunction "CLK_11") (pintype "input"))
    )
    (net (code "115") (name "MEM3-RD") (class "Default")
      (node (ref "IC17") (pin "12") (pinfunction "Y3_12") (pintype "output"))
      (node (ref "IC4") (pin "1") (pinfunction "OC_1") (pintype "input"))
    )
    (net (code "116") (name "MEM3B-LD") (class "Default")
      (node (ref "IC29") (pin "11") (pinfunction "CLK_11") (pintype "input"))
      (node (ref "IC44") (pin "12") (pinfunction "Y3_12") (pintype "output"))
    )
    (net (code "117") (name "MEM3B-RD") (class "Default")
      (node (ref "IC29") (pin "1") (pinfunction "OC_1") (pintype "input"))
      (node (ref "IC42") (pin "12") (pinfunction "Y3_12") (pintype "output"))
    )
    (net (code "118") (name "MEM4-LD") (class "Default")
      (node (ref "IC19") (pin "11") (pinfunction "Y4_11") (pintype "output"))
      (node (ref "IC5") (pin "11") (pinfunction "CLK_11") (pintype "input"))
    )
    (net (code "119") (name "MEM4-RD") (class "Default")
      (node (ref "IC17") (pin "11") (pinfunction "Y4_11") (pintype "output"))
      (node (ref "IC5") (pin "1") (pinfunction "OC_1") (pintype "input"))
    )
    (net (code "120") (name "MEM4B-LD") (class "Default")
      (node (ref "IC30") (pin "11") (pinfunction "CLK_11") (pintype "input"))
      (node (ref "IC44") (pin "11") (pinfunction "Y4_11") (pintype "output"))
    )
    (net (code "121") (name "MEM4B-RD") (class "Default")
      (node (ref "IC30") (pin "1") (pinfunction "OC_1") (pintype "input"))
      (node (ref "IC42") (pin "11") (pinfunction "Y4_11") (pintype "output"))
    )
    (net (code "122") (name "MEM5-LD") (class "Default")
      (node (ref "IC19") (pin "10") (pinfunction "Y5_10") (pintype "output"))
      (node (ref "IC6") (pin "11") (pinfunction "CLK_11") (pintype "input"))
    )
    (net (code "123") (name "MEM5-RD") (class "Default")
      (node (ref "IC17") (pin "10") (pinfunction "Y5_10") (pintype "output"))
      (node (ref "IC6") (pin "1") (pinfunction "OC_1") (pintype "input"))
    )
    (net (code "124") (name "MEM5B-LD") (class "Default")
      (node (ref "IC31") (pin "11") (pinfunction "CLK_11") (pintype "input"))
      (node (ref "IC44") (pin "10") (pinfunction "Y5_10") (pintype "output"))
    )
    (net (code "125") (name "MEM5B-RD") (class "Default")
      (node (ref "IC31") (pin "1") (pinfunction "OC_1") (pintype "input"))
      (node (ref "IC42") (pin "10") (pinfunction "Y5_10") (pintype "output"))
    )
    (net (code "126") (name "MEM6-LD") (class "Default")
      (node (ref "IC19") (pin "9") (pinfunction "Y6_9") (pintype "output"))
      (node (ref "IC7") (pin "11") (pinfunction "CLK_11") (pintype "input"))
    )
    (net (code "127") (name "MEM6-RD") (class "Default")
      (node (ref "IC17") (pin "9") (pinfunction "Y6_9") (pintype "output"))
      (node (ref "IC7") (pin "1") (pinfunction "OC_1") (pintype "input"))
    )
    (net (code "128") (name "MEM6B-LD") (class "Default")
      (node (ref "IC32") (pin "11") (pinfunction "CLK_11") (pintype "input"))
      (node (ref "IC44") (pin "9") (pinfunction "Y6_9") (pintype "output"))
    )
    (net (code "129") (name "MEM6B-RD") (class "Default")
      (node (ref "IC32") (pin "1") (pinfunction "OC_1") (pintype "input"))
      (node (ref "IC42") (pin "9") (pinfunction "Y6_9") (pintype "output"))
    )
    (net (code "130") (name "MEM7-LD") (class "Default")
      (node (ref "IC19") (pin "7") (pinfunction "Y7_7") (pintype "output"))
      (node (ref "IC8") (pin "11") (pinfunction "CLK_11") (pintype "input"))
    )
    (net (code "131") (name "MEM7-RD") (class "Default")
      (node (ref "IC17") (pin "7") (pinfunction "Y7_7") (pintype "output"))
      (node (ref "IC8") (pin "1") (pinfunction "OC_1") (pintype "input"))
    )
    (net (code "132") (name "MEM7B-LD") (class "Default")
      (node (ref "IC33") (pin "11") (pinfunction "CLK_11") (pintype "input"))
      (node (ref "IC44") (pin "7") (pinfunction "Y7_7") (pintype "output"))
    )
    (net (code "133") (name "MEM7B-RD") (class "Default")
      (node (ref "IC33") (pin "1") (pinfunction "OC_1") (pintype "input"))
      (node (ref "IC42") (pin "7") (pinfunction "Y7_7") (pintype "output"))
    )
    (net (code "134") (name "MEM8-LD") (class "Default")
      (node (ref "IC20") (pin "15") (pinfunction "Y0_15") (pintype "output"))
      (node (ref "IC9") (pin "11") (pinfunction "CLK_11") (pintype "input"))
    )
    (net (code "135") (name "MEM8-RD") (class "Default")
      (node (ref "IC18") (pin "15") (pinfunction "Y0_15") (pintype "output"))
      (node (ref "IC9") (pin "1") (pinfunction "OC_1") (pintype "input"))
    )
    (net (code "136") (name "MEM8B-LD") (class "Default")
      (node (ref "IC34") (pin "11") (pinfunction "CLK_11") (pintype "input"))
      (node (ref "IC45") (pin "15") (pinfunction "Y0_15") (pintype "output"))
    )
    (net (code "137") (name "MEM8B-RD") (class "Default")
      (node (ref "IC34") (pin "1") (pinfunction "OC_1") (pintype "input"))
      (node (ref "IC43") (pin "15") (pinfunction "Y0_15") (pintype "output"))
    )
    (net (code "138") (name "MEM9-LD") (class "Default")
      (node (ref "IC10") (pin "11") (pinfunction "CLK_11") (pintype "input"))
      (node (ref "IC20") (pin "14") (pinfunction "Y1_14") (pintype "output"))
    )
    (net (code "139") (name "MEM9-RD") (class "Default")
      (node (ref "IC10") (pin "1") (pinfunction "OC_1") (pintype "input"))
      (node (ref "IC18") (pin "14") (pinfunction "Y1_14") (pintype "output"))
    )
    (net (code "140") (name "MEM9B-LD") (class "Default")
      (node (ref "IC35") (pin "11") (pinfunction "CLK_11") (pintype "input"))
      (node (ref "IC45") (pin "14") (pinfunction "Y1_14") (pintype "output"))
    )
    (net (code "141") (name "MEM9B-RD") (class "Default")
      (node (ref "IC35") (pin "1") (pinfunction "OC_1") (pintype "input"))
      (node (ref "IC43") (pin "14") (pinfunction "Y1_14") (pintype "output"))
    )
    (net (code "142") (name "MEM10-LD") (class "Default")
      (node (ref "IC11") (pin "11") (pinfunction "CLK_11") (pintype "input"))
      (node (ref "IC20") (pin "13") (pinfunction "Y2_13") (pintype "output"))
    )
    (net (code "143") (name "MEM10-RD") (class "Default")
      (node (ref "IC11") (pin "1") (pinfunction "OC_1") (pintype "input"))
      (node (ref "IC18") (pin "13") (pinfunction "Y2_13") (pintype "output"))
    )
    (net (code "144") (name "MEM10B-LD") (class "Default")
      (node (ref "IC36") (pin "11") (pinfunction "CLK_11") (pintype "input"))
      (node (ref "IC45") (pin "13") (pinfunction "Y2_13") (pintype "output"))
    )
    (net (code "145") (name "MEM10B-RD") (class "Default")
      (node (ref "IC36") (pin "1") (pinfunction "OC_1") (pintype "input"))
      (node (ref "IC43") (pin "13") (pinfunction "Y2_13") (pintype "output"))
    )
    (net (code "146") (name "MEM11-LD") (class "Default")
      (node (ref "IC12") (pin "11") (pinfunction "CLK_11") (pintype "input"))
      (node (ref "IC20") (pin "12") (pinfunction "Y3_12") (pintype "output"))
    )
    (net (code "147") (name "MEM11-RD") (class "Default")
      (node (ref "IC12") (pin "1") (pinfunction "OC_1") (pintype "input"))
      (node (ref "IC18") (pin "12") (pinfunction "Y3_12") (pintype "output"))
    )
    (net (code "148") (name "MEM11B-LD") (class "Default")
      (node (ref "IC37") (pin "11") (pinfunction "CLK_11") (pintype "input"))
      (node (ref "IC45") (pin "12") (pinfunction "Y3_12") (pintype "output"))
    )
    (net (code "149") (name "MEM11B-RD") (class "Default")
      (node (ref "IC37") (pin "1") (pinfunction "OC_1") (pintype "input"))
      (node (ref "IC43") (pin "12") (pinfunction "Y3_12") (pintype "output"))
    )
    (net (code "150") (name "MEM12-LD") (class "Default")
      (node (ref "IC13") (pin "11") (pinfunction "CLK_11") (pintype "input"))
      (node (ref "IC20") (pin "11") (pinfunction "Y4_11") (pintype "output"))
    )
    (net (code "151") (name "MEM12-RD") (class "Default")
      (node (ref "IC13") (pin "1") (pinfunction "OC_1") (pintype "input"))
      (node (ref "IC18") (pin "11") (pinfunction "Y4_11") (pintype "output"))
    )
    (net (code "152") (name "MEM12B-LD") (class "Default")
      (node (ref "IC38") (pin "11") (pinfunction "CLK_11") (pintype "input"))
      (node (ref "IC45") (pin "11") (pinfunction "Y4_11") (pintype "output"))
    )
    (net (code "153") (name "MEM12B-RD") (class "Default")
      (node (ref "IC38") (pin "1") (pinfunction "OC_1") (pintype "input"))
      (node (ref "IC43") (pin "11") (pinfunction "Y4_11") (pintype "output"))
    )
    (net (code "154") (name "MEM13-LD") (class "Default")
      (node (ref "IC14") (pin "11") (pinfunction "CLK_11") (pintype "input"))
      (node (ref "IC20") (pin "10") (pinfunction "Y5_10") (pintype "output"))
    )
    (net (code "155") (name "MEM13-RD") (class "Default")
      (node (ref "IC14") (pin "1") (pinfunction "OC_1") (pintype "input"))
      (node (ref "IC18") (pin "10") (pinfunction "Y5_10") (pintype "output"))
    )
    (net (code "156") (name "MEM13B-LD") (class "Default")
      (node (ref "IC39") (pin "11") (pinfunction "CLK_11") (pintype "input"))
      (node (ref "IC45") (pin "10") (pinfunction "Y5_10") (pintype "output"))
    )
    (net (code "157") (name "MEM13B-RD") (class "Default")
      (node (ref "IC39") (pin "1") (pinfunction "OC_1") (pintype "input"))
      (node (ref "IC43") (pin "10") (pinfunction "Y5_10") (pintype "output"))
    )
    (net (code "158") (name "MEM14-LD") (class "Default")
      (node (ref "IC15") (pin "11") (pinfunction "CLK_11") (pintype "input"))
      (node (ref "IC20") (pin "9") (pinfunction "Y6_9") (pintype "output"))
    )
    (net (code "159") (name "MEM14-RD") (class "Default")
      (node (ref "IC15") (pin "1") (pinfunction "OC_1") (pintype "input"))
      (node (ref "IC18") (pin "9") (pinfunction "Y6_9") (pintype "output"))
    )
    (net (code "160") (name "MEM14B-LD") (class "Default")
      (node (ref "IC40") (pin "11") (pinfunction "CLK_11") (pintype "input"))
      (node (ref "IC45") (pin "9") (pinfunction "Y6_9") (pintype "output"))
    )
    (net (code "161") (name "MEM14B-RD") (class "Default")
      (node (ref "IC40") (pin "1") (pinfunction "OC_1") (pintype "input"))
      (node (ref "IC43") (pin "9") (pinfunction "Y6_9") (pintype "output"))
    )
    (net (code "162") (name "MEM15-LD") (class "Default")
      (node (ref "IC16") (pin "11") (pinfunction "CLK_11") (pintype "input"))
      (node (ref "IC20") (pin "7") (pinfunction "Y7_7") (pintype "output"))
    )
    (net (code "163") (name "MEM15-RD") (class "Default")
      (node (ref "IC16") (pin "1") (pinfunction "OC_1") (pintype "input"))
      (node (ref "IC18") (pin "7") (pinfunction "Y7_7") (pintype "output"))
    )
    (net (code "164") (name "MEM15B-LD") (class "Default")
      (node (ref "IC41") (pin "11") (pinfunction "CLK_11") (pintype "input"))
      (node (ref "IC45") (pin "7") (pinfunction "Y7_7") (pintype "output"))
    )
    (net (code "165") (name "MEM15B-RD") (class "Default")
      (node (ref "IC41") (pin "1") (pinfunction "OC_1") (pintype "input"))
      (node (ref "IC43") (pin "7") (pinfunction "Y7_7") (pintype "output"))
    )
    (net (code "166") (name "Net-(IC22A-G)") (class "Default")
      (node (ref "IC22") (pin "1") (pinfunction "G_1") (pintype "input"))
      (node (ref "IC22") (pin "19") (pinfunction "G_19") (pintype "input"))
      (node (ref "IC23") (pin "3") (pinfunction "O_3") (pintype "output"))
    )
    (net (code "167") (name "Net-(IC23D-O)") (class "Default")
      (node (ref "IC23") (pin "11") (pinfunction "O_11") (pintype "output"))
      (node (ref "IC47") (pin "1") (pinfunction "G_1") (pintype "input"))
      (node (ref "IC47") (pin "19") (pinfunction "G_19") (pintype "input"))
    )
    (net (code "168") (name "Net-(IC25A-Y0)") (class "Default")
      (node (ref "IC25") (pin "4") (pinfunction "Y0_4") (pintype "output"))
      (node (ref "SV1") (pin "8") (pinfunction "8_8") (pintype "passive"))
    )
    (net (code "169") (name "Net-(IC25A-Y1)") (class "Default")
      (node (ref "IC25") (pin "5") (pinfunction "Y1_5") (pintype "output"))
      (node (ref "SV1") (pin "6") (pinfunction "6_6") (pintype "passive"))
    )
    (net (code "170") (name "Net-(IC25A-Y2)") (class "Default")
      (node (ref "IC25") (pin "6") (pinfunction "Y2_6") (pintype "output"))
      (node (ref "SV1") (pin "4") (pinfunction "4_4") (pintype "passive"))
    )
    (net (code "171") (name "Net-(IC25A-Y3)") (class "Default")
      (node (ref "IC25") (pin "7") (pinfunction "Y3_7") (pintype "output"))
      (node (ref "SV1") (pin "2") (pinfunction "2_2") (pintype "passive"))
    )
    (net (code "172") (name "Net-(IC25B-Y0)") (class "Default")
      (node (ref "IC25") (pin "12") (pinfunction "Y0_12") (pintype "output"))
      (node (ref "SV2") (pin "8") (pinfunction "8_8") (pintype "passive"))
    )
    (net (code "173") (name "Net-(IC25B-Y1)") (class "Default")
      (node (ref "IC25") (pin "11") (pinfunction "Y1_11") (pintype "output"))
      (node (ref "SV2") (pin "6") (pinfunction "6_6") (pintype "passive"))
    )
    (net (code "174") (name "Net-(IC25B-Y2)") (class "Default")
      (node (ref "IC25") (pin "10") (pinfunction "Y2_10") (pintype "output"))
      (node (ref "SV2") (pin "4") (pinfunction "4_4") (pintype "passive"))
    )
    (net (code "175") (name "Net-(IC25B-Y3)") (class "Default")
      (node (ref "IC25") (pin "9") (pinfunction "Y3_9") (pintype "output"))
      (node (ref "SV2") (pin "2") (pinfunction "2_2") (pintype "passive"))
    )
    (net (code "176") (name "Net-(PWR-PadA)") (class "Default")
      (node (ref "PWR") (pin "A") (pinfunction "A_A") (pintype "passive"))
      (node (ref "R1") (pin "1") (pinfunction "1_1") (pintype "passive"))
    )
    (net (code "177") (name "OUT") (class "Default")
      (node (ref "X1") (pin "C27") (pinfunction "B_C27") (pintype "passive"))
    )
    (net (code "178") (name "REG-BRD-LD-ID") (class "Default")
      (node (ref "X1") (pin "B16") (pinfunction "B_B16") (pintype "passive"))
    )
    (net (code "179") (name "REG-BRD-RD-ID") (class "Default")
      (node (ref "X1") (pin "B12") (pinfunction "B_B12") (pintype "passive"))
    )
    (net (code "180") (name "REG-FUNC-LD") (class "Default")
      (node (ref "X1") (pin "B7") (pinfunction "B_B7") (pintype "passive"))
    )
    (net (code "181") (name "REG-FUNC-RD") (class "Default")
      (node (ref "X1") (pin "B8") (pinfunction "B_B8") (pintype "passive"))
    )
    (net (code "182") (name "REG-LD-HI") (class "Default")
      (node (ref "X1") (pin "B23") (pinfunction "B_B23") (pintype "passive"))
    )
    (net (code "183") (name "REG-LD-ID0") (class "Default")
      (node (ref "X1") (pin "B17") (pinfunction "B_B17") (pintype "passive"))
    )
    (net (code "184") (name "REG-LD-ID1") (class "Default")
      (node (ref "X1") (pin "B18") (pinfunction "B_B18") (pintype "passive"))
    )
    (net (code "185") (name "REG-LD-ID2") (class "Default")
      (node (ref "X1") (pin "B19") (pinfunction "B_B19") (pintype "passive"))
    )
    (net (code "186") (name "REG-LD-LO") (class "Default")
      (node (ref "X1") (pin "B21") (pinfunction "B_B21") (pintype "passive"))
    )
    (net (code "187") (name "REG-RD-HI") (class "Default")
      (node (ref "X1") (pin "B22") (pinfunction "B_B22") (pintype "passive"))
    )
    (net (code "188") (name "REG-RD-ID0") (class "Default")
      (node (ref "X1") (pin "B13") (pinfunction "B_B13") (pintype "passive"))
    )
    (net (code "189") (name "REG-RD-ID1") (class "Default")
      (node (ref "X1") (pin "B14") (pinfunction "B_B14") (pintype "passive"))
    )
    (net (code "190") (name "REG-RD-ID2") (class "Default")
      (node (ref "X1") (pin "B15") (pinfunction "B_B15") (pintype "passive"))
    )
    (net (code "191") (name "REG-RD-LO") (class "Default")
      (node (ref "X1") (pin "B20") (pinfunction "B_B20") (pintype "passive"))
    )
    (net (code "192") (name "RESET") (class "Default")
      (node (ref "X1") (pin "C30") (pinfunction "B_C30") (pintype "passive"))
    )
    (net (code "193") (name "RUN") (class "Default")
      (node (ref "X1") (pin "C29") (pinfunction "B_C29") (pintype "passive"))
    )
    (net (code "194") (name "SR-LD") (class "Default")
      (node (ref "X1") (pin "C23") (pinfunction "B_C23") (pintype "passive"))
    )
    (net (code "195") (name "TMP-REG-LD") (class "Default")
      (node (ref "X1") (pin "C3") (pinfunction "B_C3") (pintype "passive"))
    )
    (net (code "196") (name "TMP-REG-RD") (class "Default")
      (node (ref "X1") (pin "C4") (pinfunction "B_C4") (pintype "passive"))
    )
    (net (code "197") (name "UNUSED1") (class "Default")
      (node (ref "X1") (pin "B11") (pinfunction "B_B11") (pintype "passive"))
    )
    (net (code "198") (name "UNUSED2") (class "Default")
      (node (ref "X1") (pin "C5") (pinfunction "B_C5") (pintype "passive"))
    )
    (net (code "199") (name "VCC") (class "Default")
      (node (ref "R1") (pin "2") (pinfunction "2_2") (pintype "passive"))
      (node (ref "X1") (pin "A2") (pinfunction "B_A2") (pintype "passive"))
      (node (ref "X1") (pin "A31") (pinfunction "B_A31") (pintype "passive"))
      (node (ref "X1") (pin "B2") (pinfunction "B_B2") (pintype "passive"))
      (node (ref "X1") (pin "B31") (pinfunction "B_B31") (pintype "passive"))
      (node (ref "X1") (pin "C2") (pinfunction "B_C2") (pintype "passive"))
      (node (ref "X1") (pin "C31") (pinfunction "B_C31") (pintype "passive"))
    )
    (net (code "200") (name "unconnected-(IC23B-O-Pad6)") (class "Default")
      (node (ref "IC23") (pin "6") (pinfunction "O_6") (pintype "output"))
    )
    (net (code "201") (name "unconnected-(IC23C-O-Pad8)") (class "Default")
      (node (ref "IC23") (pin "8") (pinfunction "O_8") (pintype "output"))
    )
    (net (code "202") (name "unconnected-(IC24E-O-Pad10)") (class "Default")
      (node (ref "IC24") (pin "10") (pinfunction "O_10") (pintype "output"))
    )
    (net (code "203") (name "unconnected-(IC24F-O-Pad12)") (class "Default")
      (node (ref "IC24") (pin "12") (pinfunction "O_12") (pintype "output"))
    )
  )
)
